# Spectre-SCH_SH2__rev.net
KiCad netlist of a schematic drawn in Altium Designer
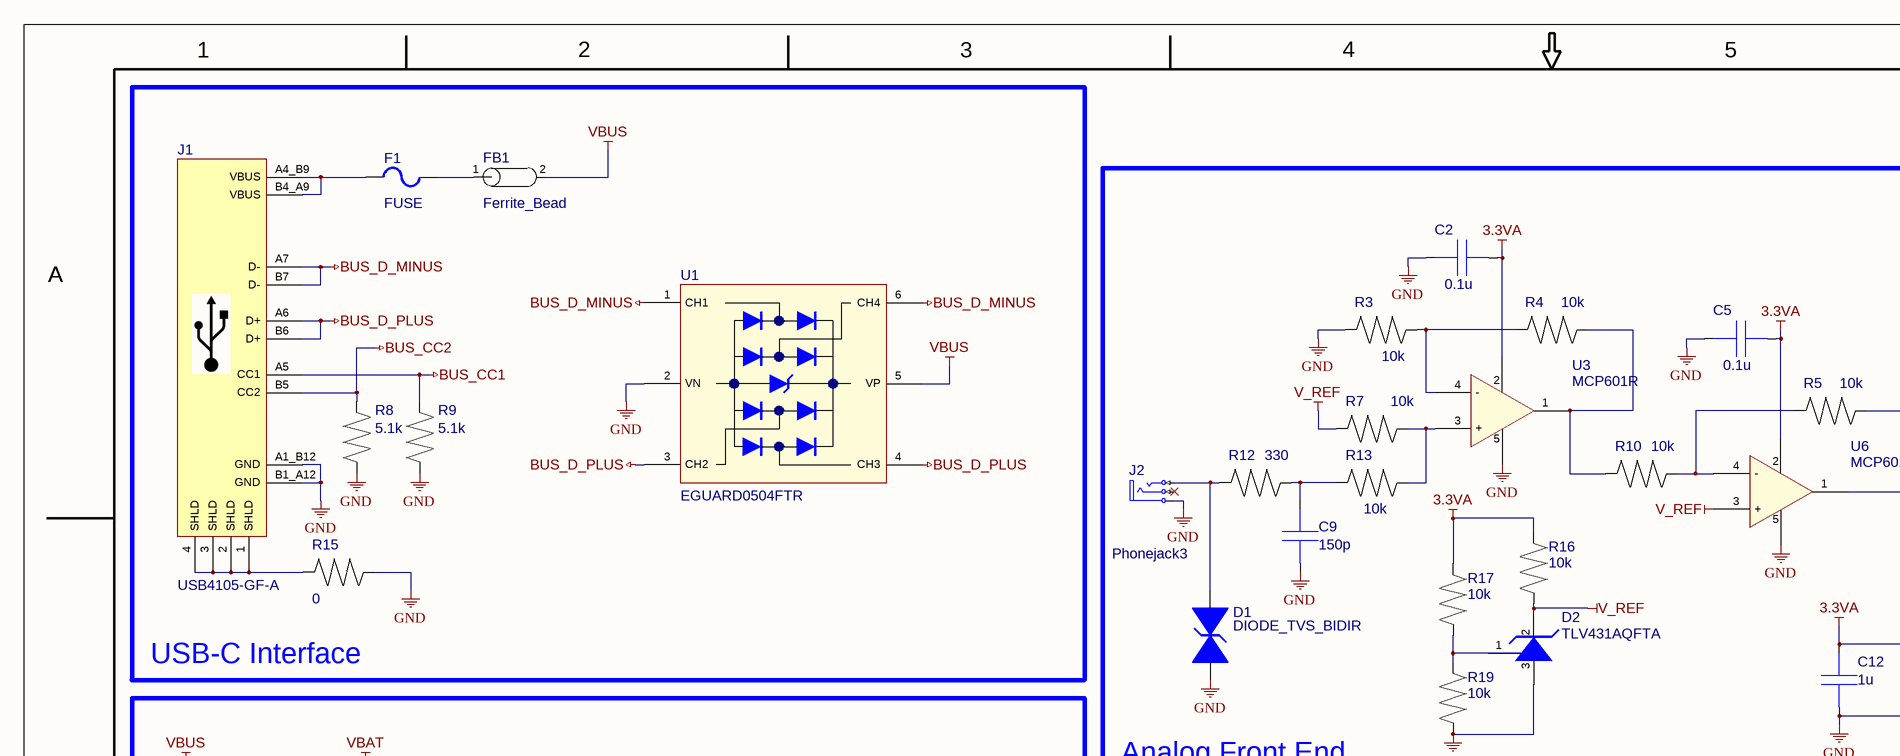
[diagram p0: Spectre-SCH_SH2_(rev).SchDoc, top left]
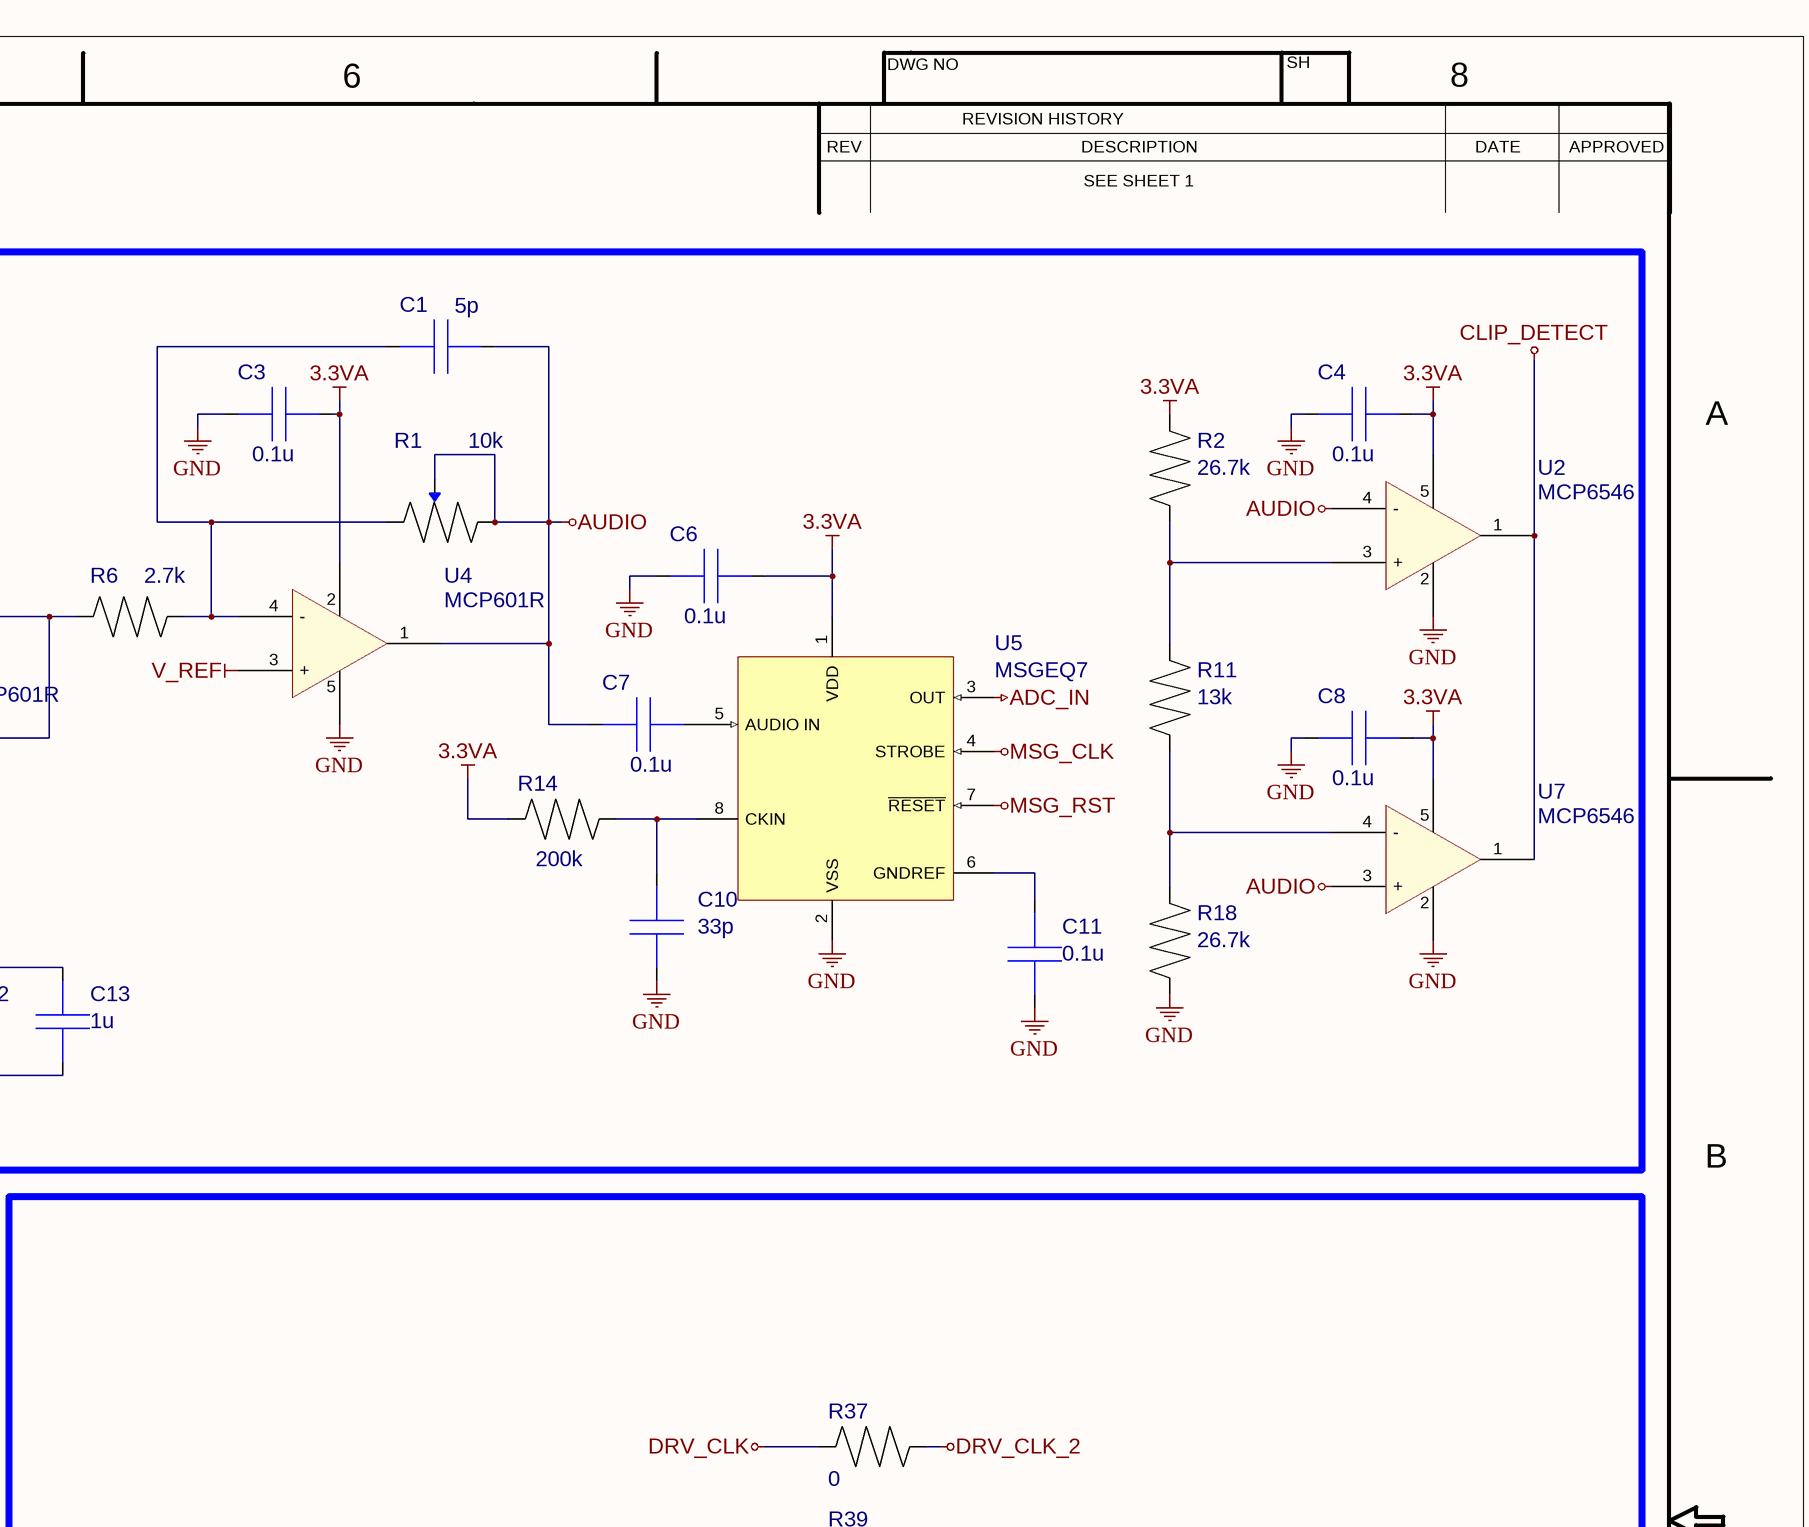
[diagram p1: Spectre-SCH_SH2_(rev).SchDoc, top right]
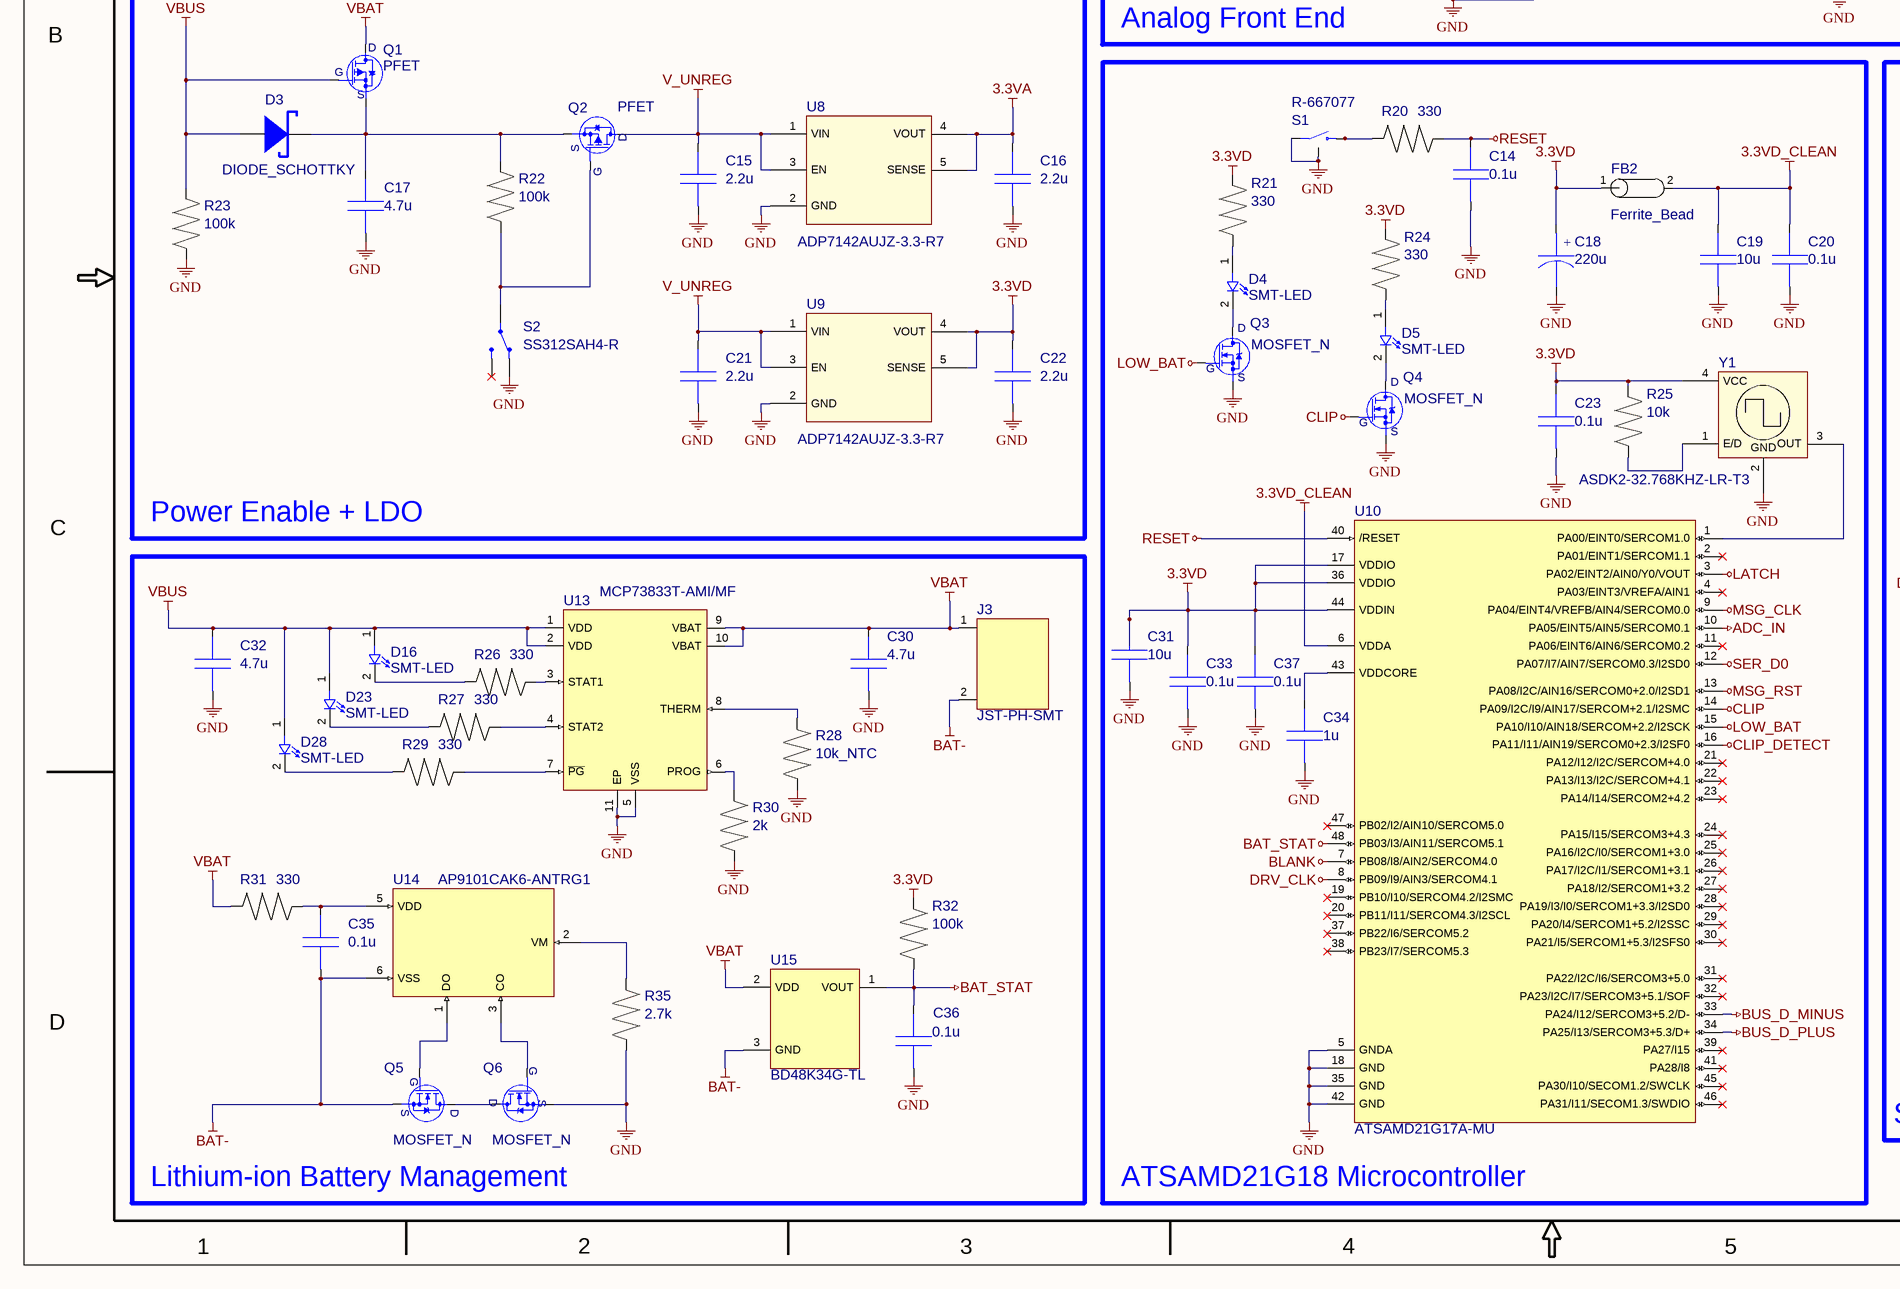
[diagram p2: Spectre-SCH_SH2_(rev).SchDoc, bottom left]
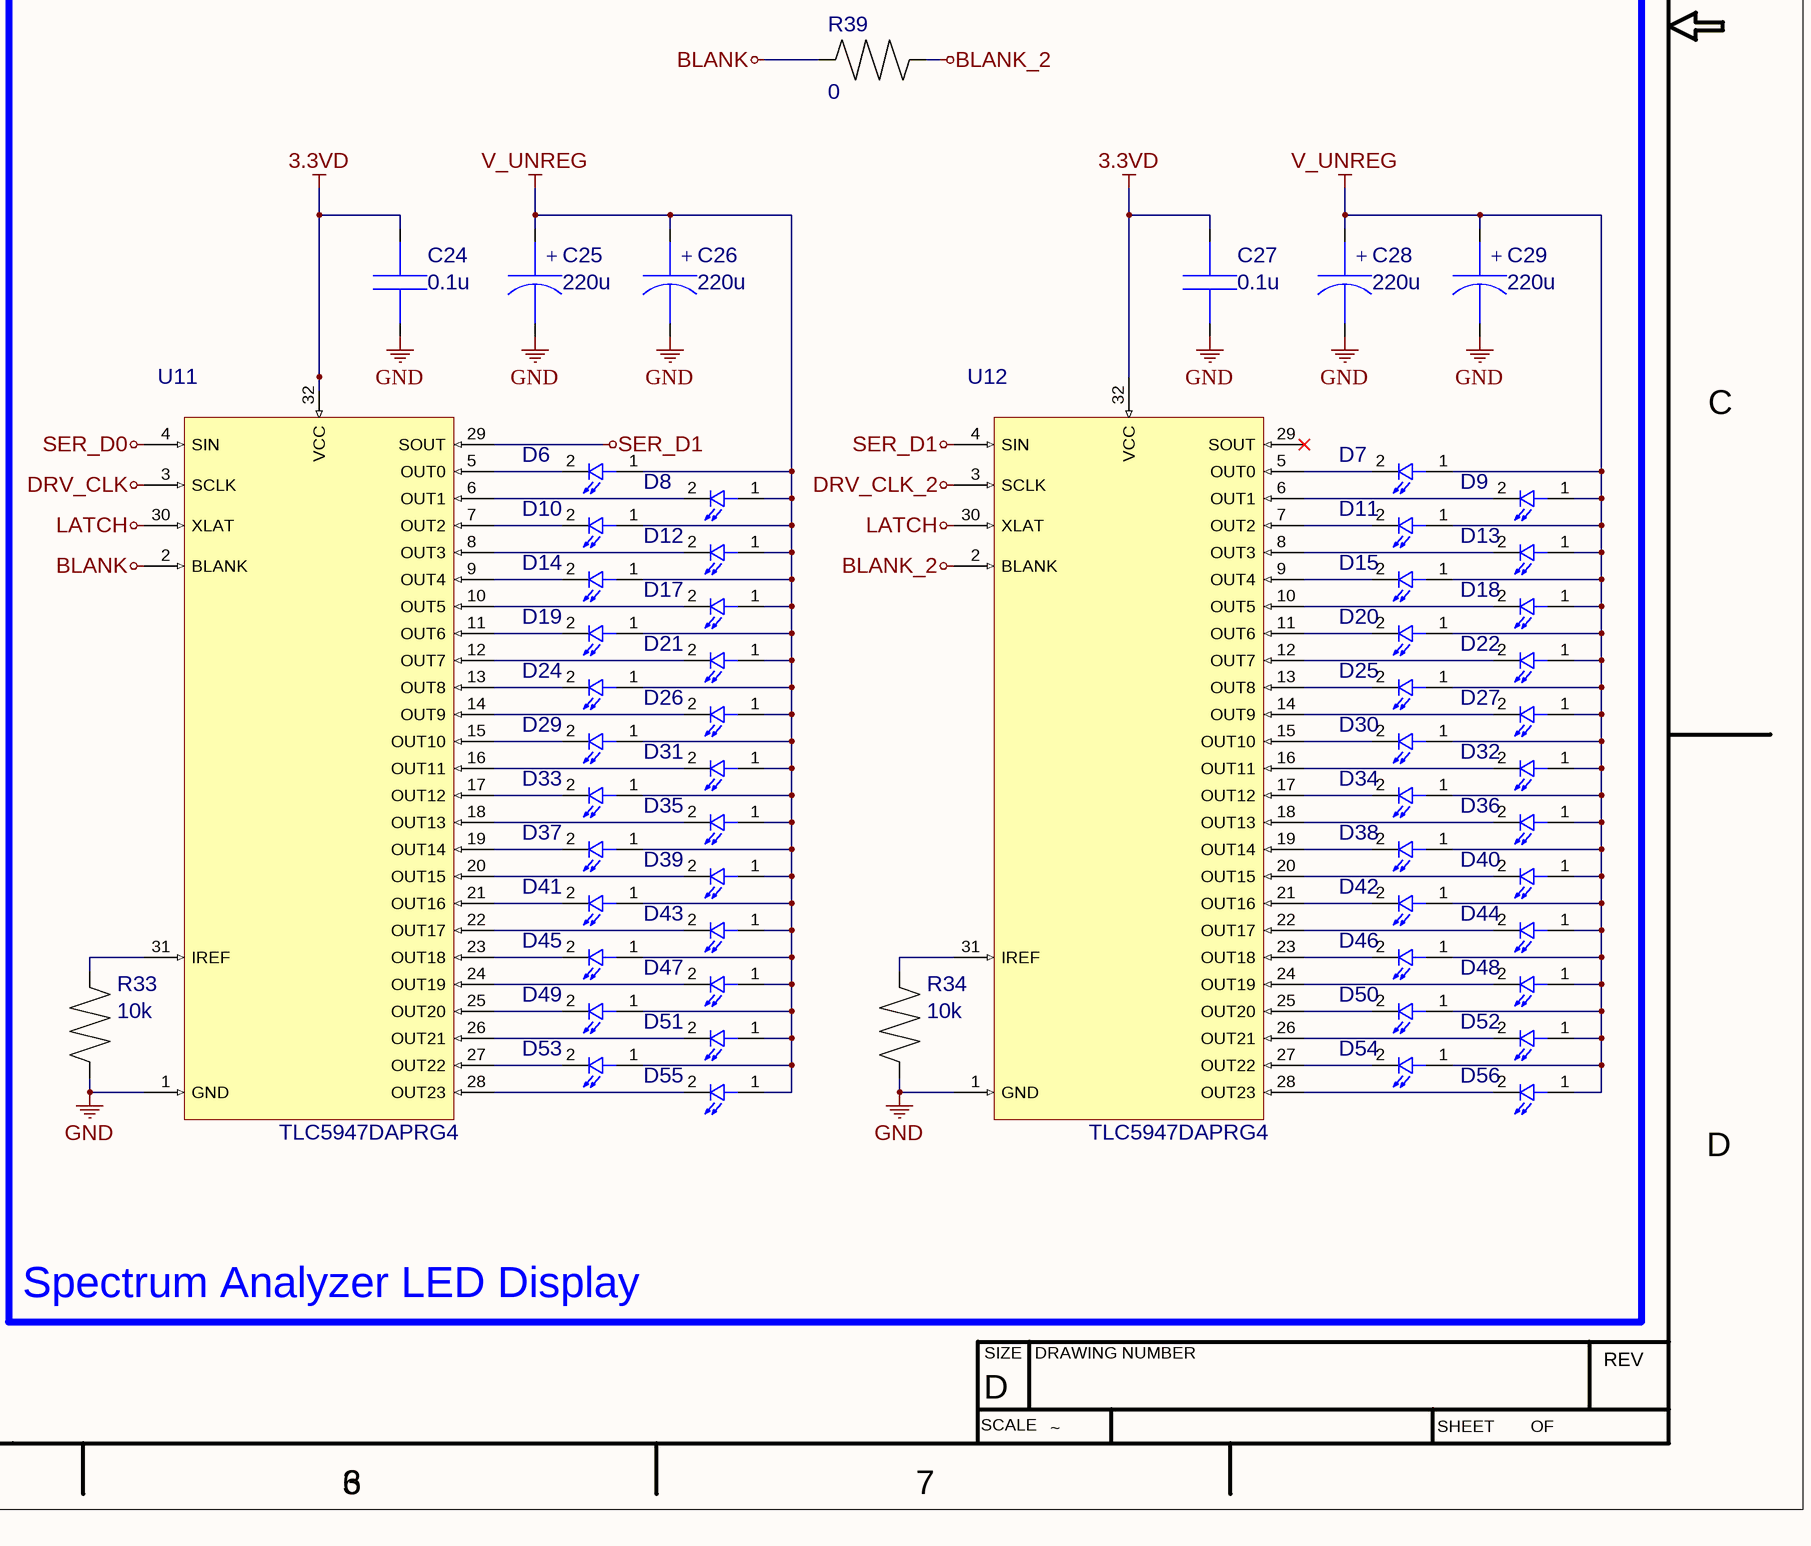
[diagram p3: Spectre-SCH_SH2_(rev).SchDoc, bottom right]

(export (version "E")
  (design (tool "Eeschema 10.0.6"))
  (components
    (comp (ref "C1") (value "5p") (footprint "0805") (libsource (lib "CAPACITORS") (part "CAP")))
    (comp (ref "C2") (value "0.1u") (footprint "0805") (libsource (lib "CAPACITORS") (part "CAP")))
    (comp (ref "C3") (value "0.1u") (footprint "0805") (libsource (lib "CAPACITORS") (part "CAP")))
    (comp (ref "C4") (value "0.1u") (footprint "0805") (libsource (lib "CAPACITORS") (part "CAP")))
    (comp (ref "C5") (value "0.1u") (footprint "0805") (libsource (lib "CAPACITORS") (part "CAP")))
    (comp (ref "C6") (value "0.1u") (footprint "0805") (libsource (lib "CAPACITORS") (part "CAP")))
    (comp (ref "C7") (value "0.1u") (footprint "0805") (libsource (lib "CAPACITORS") (part "CAP")))
    (comp (ref "C8") (value "0.1u") (footprint "0805") (libsource (lib "CAPACITORS") (part "CAP")))
    (comp (ref "C9") (value "150p") (footprint "0805") (libsource (lib "CAPACITORS") (part "CAP")))
    (comp (ref "C10") (value "33p") (footprint "0805") (libsource (lib "CAPACITORS") (part "CAP")))
    (comp (ref "C11") (value "0.1u") (footprint "0805") (libsource (lib "CAPACITORS") (part "CAP")))
    (comp (ref "C12") (value "1u") (footprint "0805") (libsource (lib "CAPACITORS") (part "CAP")))
    (comp (ref "C13") (value "1u") (footprint "0805") (libsource (lib "CAPACITORS") (part "CAP")))
    (comp (ref "C14") (value "0.1u") (footprint "0805") (libsource (lib "CAPACITORS") (part "CAP")))
    (comp (ref "C15") (value "2.2u") (footprint "0805") (libsource (lib "CAPACITORS") (part "CAP")))
    (comp (ref "C16") (value "2.2u") (footprint "0805") (libsource (lib "CAPACITORS") (part "CAP")))
    (comp (ref "C17") (value "4.7u") (footprint "0603") (libsource (lib "CAPACITORS") (part "CAP")))
    (comp (ref "C18")
      (value "220u")
      (footprint "D")
      (description "CAP TANT POLY 220UF 6.3V 2917")
      (fields (field (name "MANUFACTURER") "KEMET") (field (name "PART NUMBER") "T525D227M006ATE025"))
      (libsource (lib "CAPACITORS") (part "CAP_POL"))
    )
    (comp (ref "C19") (value "10u") (footprint "0805") (libsource (lib "CAPACITORS") (part "CAP")))
    (comp (ref "C20") (value "0.1u") (footprint "0805") (libsource (lib "CAPACITORS") (part "CAP")))
    (comp (ref "C21") (value "2.2u") (footprint "0805") (libsource (lib "CAPACITORS") (part "CAP")))
    (comp (ref "C22") (value "2.2u") (footprint "0805") (libsource (lib "CAPACITORS") (part "CAP")))
    (comp (ref "C23") (value "0.1u") (footprint "0805") (libsource (lib "CAPACITORS") (part "CAP")))
    (comp (ref "C24") (value "0.1u") (footprint "0805") (libsource (lib "CAPACITORS") (part "CAP")))
    (comp (ref "C25")
      (value "220u")
      (footprint "D")
      (description "CAP TANT POLY 220UF 6.3V 2917")
      (fields (field (name "MANUFACTURER") "KEMET") (field (name "PART NUMBER") "T525D227M006ATE025"))
      (libsource (lib "CAPACITORS") (part "CAP_POL"))
    )
    (comp (ref "C26")
      (value "220u")
      (footprint "D")
      (description "CAP TANT POLY 220UF 6.3V 2917")
      (fields (field (name "MANUFACTURER") "KEMET") (field (name "PART NUMBER") "T525D227M006ATE025"))
      (libsource (lib "CAPACITORS") (part "CAP_POL"))
    )
    (comp (ref "C27") (value "0.1u") (footprint "0805") (libsource (lib "CAPACITORS") (part "CAP")))
    (comp (ref "C28")
      (value "220u")
      (footprint "D")
      (description "CAP TANT POLY 220UF 6.3V 2917")
      (fields (field (name "MANUFACTURER") "KEMET") (field (name "PART NUMBER") "T525D227M006ATE025"))
      (libsource (lib "CAPACITORS") (part "CAP_POL"))
    )
    (comp (ref "C29")
      (value "220u")
      (footprint "D")
      (description "CAP TANT POLY 220UF 6.3V 2917")
      (fields (field (name "MANUFACTURER") "KEMET") (field (name "PART NUMBER") "T525D227M006ATE025"))
      (libsource (lib "CAPACITORS") (part "CAP_POL"))
    )
    (comp (ref "C30") (value "4.7u") (footprint "0603") (libsource (lib "CAPACITORS") (part "CAP")))
    (comp (ref "C31") (value "10u") (footprint "1206") (libsource (lib "CAPACITORS") (part "CAP")))
    (comp (ref "C32") (value "4.7u") (footprint "0603") (libsource (lib "CAPACITORS") (part "CAP")))
    (comp (ref "C33") (value "0.1u") (footprint "0805") (libsource (lib "CAPACITORS") (part "CAP")))
    (comp (ref "C34") (value "1u") (footprint "0805") (libsource (lib "CAPACITORS") (part "CAP")))
    (comp (ref "C35") (value "0.1u") (footprint "0805") (libsource (lib "CAPACITORS") (part "CAP")))
    (comp (ref "C36") (value "0.1u") (footprint "0805") (libsource (lib "CAPACITORS") (part "CAP")))
    (comp (ref "C37") (value "0.1u") (footprint "0805") (libsource (lib "CAPACITORS") (part "CAP")))
    (comp (ref "D1")
      (value "DIODE_TVS_BIDIR")
      (footprint "0603")
      (description "TVS DIODE BIDIR")
      (libsource (lib "SEMICONDUCTORS") (part "DIODE_TVS_BIDIR"))
    )
    (comp (ref "D2")
      (value "TLV431AQFTA")
      (footprint "SOT-23-3")
      (description "Shunt Voltage Reference IC Adjustable 1.24V 18 VV ±1% 15 mA SOT-23-3")
      (fields (field (name "MANUFACTURER") "Diodes Incorporated"))
      (libsource (lib "TLV431AQFTA") (part "TLV431AQFTA"))
    )
    (comp (ref "D3")
      (value "DIODE_SCHOTTKY")
      (footprint "SMA")
      (description "DIODE SCHOTTKY")
      (libsource (lib "SEMICONDUCTORS") (part "DIODE_SCHOTTKY"))
    )
    (comp (ref "D4") (value "SMT-LED") (footprint "0805 LED") (libsource (lib "SMT-LED") (part "SMT-LED")))
    (comp (ref "D5") (value "SMT-LED") (footprint "0805 LED") (libsource (lib "SMT-LED") (part "SMT-LED")))
    (comp (ref "D6") (value "SMT-LED") (footprint "0805 LED") (libsource (lib "SMT-LED") (part "SMT-LED")))
    (comp (ref "D7") (value "SMT-LED") (footprint "0805 LED") (libsource (lib "SMT-LED") (part "SMT-LED")))
    (comp (ref "D8") (value "SMT-LED") (footprint "0805 LED") (libsource (lib "SMT-LED") (part "SMT-LED")))
    (comp (ref "D9") (value "SMT-LED") (footprint "0805 LED") (libsource (lib "SMT-LED") (part "SMT-LED")))
    (comp (ref "D10") (value "SMT-LED") (footprint "0805 LED") (libsource (lib "SMT-LED") (part "SMT-LED")))
    (comp (ref "D11") (value "SMT-LED") (footprint "0805 LED") (libsource (lib "SMT-LED") (part "SMT-LED")))
    (comp (ref "D12") (value "SMT-LED") (footprint "0805 LED") (libsource (lib "SMT-LED") (part "SMT-LED")))
    (comp (ref "D13") (value "SMT-LED") (footprint "0805 LED") (libsource (lib "SMT-LED") (part "SMT-LED")))
    (comp (ref "D14") (value "SMT-LED") (footprint "0805 LED") (libsource (lib "SMT-LED") (part "SMT-LED")))
    (comp (ref "D15") (value "SMT-LED") (footprint "0805 LED") (libsource (lib "SMT-LED") (part "SMT-LED")))
    (comp (ref "D16") (value "SMT-LED") (footprint "0805 LED") (libsource (lib "SMT-LED") (part "SMT-LED")))
    (comp (ref "D17") (value "SMT-LED") (footprint "0805 LED") (libsource (lib "SMT-LED") (part "SMT-LED")))
    (comp (ref "D18") (value "SMT-LED") (footprint "0805 LED") (libsource (lib "SMT-LED") (part "SMT-LED")))
    (comp (ref "D19") (value "SMT-LED") (footprint "0805 LED") (libsource (lib "SMT-LED") (part "SMT-LED")))
    (comp (ref "D20") (value "SMT-LED") (footprint "0805 LED") (libsource (lib "SMT-LED") (part "SMT-LED")))
    (comp (ref "D21") (value "SMT-LED") (footprint "0805 LED") (libsource (lib "SMT-LED") (part "SMT-LED")))
    (comp (ref "D22") (value "SMT-LED") (footprint "0805 LED") (libsource (lib "SMT-LED") (part "SMT-LED")))
    (comp (ref "D23") (value "SMT-LED") (footprint "0805 LED") (libsource (lib "SMT-LED") (part "SMT-LED")))
    (comp (ref "D24") (value "SMT-LED") (footprint "0805 LED") (libsource (lib "SMT-LED") (part "SMT-LED")))
    (comp (ref "D25") (value "SMT-LED") (footprint "0805 LED") (libsource (lib "SMT-LED") (part "SMT-LED")))
    (comp (ref "D26") (value "SMT-LED") (footprint "0805 LED") (libsource (lib "SMT-LED") (part "SMT-LED")))
    (comp (ref "D27") (value "SMT-LED") (footprint "0805 LED") (libsource (lib "SMT-LED") (part "SMT-LED")))
    (comp (ref "D28") (value "SMT-LED") (footprint "0805 LED") (libsource (lib "SMT-LED") (part "SMT-LED")))
    (comp (ref "D29") (value "SMT-LED") (footprint "0805 LED") (libsource (lib "SMT-LED") (part "SMT-LED")))
    (comp (ref "D30") (value "SMT-LED") (footprint "0805 LED") (libsource (lib "SMT-LED") (part "SMT-LED")))
    (comp (ref "D31") (value "SMT-LED") (footprint "0805 LED") (libsource (lib "SMT-LED") (part "SMT-LED")))
    (comp (ref "D32") (value "SMT-LED") (footprint "0805 LED") (libsource (lib "SMT-LED") (part "SMT-LED")))
    (comp (ref "D33") (value "SMT-LED") (footprint "0805 LED") (libsource (lib "SMT-LED") (part "SMT-LED")))
    (comp (ref "D34") (value "SMT-LED") (footprint "0805 LED") (libsource (lib "SMT-LED") (part "SMT-LED")))
    (comp (ref "D35") (value "SMT-LED") (footprint "0805 LED") (libsource (lib "SMT-LED") (part "SMT-LED")))
    (comp (ref "D36") (value "SMT-LED") (footprint "0805 LED") (libsource (lib "SMT-LED") (part "SMT-LED")))
    (comp (ref "D37") (value "SMT-LED") (footprint "0805 LED") (libsource (lib "SMT-LED") (part "SMT-LED")))
    (comp (ref "D38") (value "SMT-LED") (footprint "0805 LED") (libsource (lib "SMT-LED") (part "SMT-LED")))
    (comp (ref "D39") (value "SMT-LED") (footprint "0805 LED") (libsource (lib "SMT-LED") (part "SMT-LED")))
    (comp (ref "D40") (value "SMT-LED") (footprint "0805 LED") (libsource (lib "SMT-LED") (part "SMT-LED")))
    (comp (ref "D41") (value "SMT-LED") (footprint "0805 LED") (libsource (lib "SMT-LED") (part "SMT-LED")))
    (comp (ref "D42") (value "SMT-LED") (footprint "0805 LED") (libsource (lib "SMT-LED") (part "SMT-LED")))
    (comp (ref "D43") (value "SMT-LED") (footprint "0805 LED") (libsource (lib "SMT-LED") (part "SMT-LED")))
    (comp (ref "D44") (value "SMT-LED") (footprint "0805 LED") (libsource (lib "SMT-LED") (part "SMT-LED")))
    (comp (ref "D45") (value "SMT-LED") (footprint "0805 LED") (libsource (lib "SMT-LED") (part "SMT-LED")))
    (comp (ref "D46") (value "SMT-LED") (footprint "0805 LED") (libsource (lib "SMT-LED") (part "SMT-LED")))
    (comp (ref "D47") (value "SMT-LED") (footprint "0805 LED") (libsource (lib "SMT-LED") (part "SMT-LED")))
    (comp (ref "D48") (value "SMT-LED") (footprint "0805 LED") (libsource (lib "SMT-LED") (part "SMT-LED")))
    (comp (ref "D49") (value "SMT-LED") (footprint "0805 LED") (libsource (lib "SMT-LED") (part "SMT-LED")))
    (comp (ref "D50") (value "SMT-LED") (footprint "0805 LED") (libsource (lib "SMT-LED") (part "SMT-LED")))
    (comp (ref "D51") (value "SMT-LED") (footprint "0805 LED") (libsource (lib "SMT-LED") (part "SMT-LED")))
    (comp (ref "D52") (value "SMT-LED") (footprint "0805 LED") (libsource (lib "SMT-LED") (part "SMT-LED")))
    (comp (ref "D53") (value "SMT-LED") (footprint "0805 LED") (libsource (lib "SMT-LED") (part "SMT-LED")))
    (comp (ref "D54") (value "SMT-LED") (footprint "0805 LED") (libsource (lib "SMT-LED") (part "SMT-LED")))
    (comp (ref "D55") (value "SMT-LED") (footprint "0805 LED") (libsource (lib "SMT-LED") (part "SMT-LED")))
    (comp (ref "D56") (value "SMT-LED") (footprint "0805 LED") (libsource (lib "SMT-LED") (part "SMT-LED")))
    (comp (ref "F1") (value "FUSE") (footprint "1206") (libsource (lib "Power") (part "FUSE")))
    (comp (ref "FB1")
      (value "Ferrite_Bead")
      (footprint "0805")
      (description "Ferrite Bead")
      (libsource (lib "Ferrite_Beads") (part "Ferrite_Bead"))
    )
    (comp (ref "FB2")
      (value "Ferrite_Bead")
      (footprint "0805")
      (description "Ferrite Bead")
      (libsource (lib "Ferrite_Beads") (part "Ferrite_Bead"))
    )
    (comp (ref "J1")
      (value "USB4105-GF-A")
      (footprint "USB4105-GF-A")
      (fields (field (name "MANUFACTURER") "GCT"))
      (libsource (lib "USB4105-GF-A") (part "USB4105-GF-A"))
    )
    (comp (ref "J2")
      (value "Phonejack3")
      (footprint "STX-3500-3NTR")
      (description "Jack Socket, 1/4\" [6.5mm], Thru-Hole, Vertical, 3-Conductor Open Circuit (Non-Normalling)")
      (fields (field (name "PUBLISHER") "Altium Limited"))
      (libsource (lib "Miscellaneous Connectors") (part "Phonejack3"))
    )
    (comp (ref "J3")
      (value "JST-PH-SMT")
      (footprint "JST-PH-SMT")
      (libsource (lib "JST-PH-SMT") (part "JST-PH-SMT"))
    )
    (comp (ref "Q1")
      (value "PFET")
      (footprint "TO-252-3")
      (description "MOSFET, P CH, 3-PIN")
      (libsource (lib "SEMICONDUCTORS") (part "MOSFET_P"))
    )
    (comp (ref "Q2")
      (value "PFET")
      (footprint "TO-252-3")
      (description "MOSFET, P CH, 3-PIN")
      (libsource (lib "") (part "MOSFET_P_1"))
    )
    (comp (ref "Q3")
      (value "MOSFET_N")
      (footprint "SOT-23")
      (description "MOSFET, N CH, 3-PIN")
      (libsource (lib "") (part "MOSFET_N_2"))
    )
    (comp (ref "Q4")
      (value "MOSFET_N")
      (footprint "SOT-23")
      (description "MOSFET, N CH, 3-PIN")
      (libsource (lib "") (part "MOSFET_N_2"))
    )
    (comp (ref "Q5")
      (value "MOSFET_N")
      (footprint "SOT-23")
      (description "MOSFET, N CH, 3-PIN")
      (libsource (lib "SEMICONDUCTORS") (part "MOSFET_N"))
    )
    (comp (ref "Q6")
      (value "MOSFET_N")
      (footprint "SOT-23")
      (description "MOSFET, N CH, 3-PIN")
      (libsource (lib "") (part "MOSFET_N_1"))
    )
    (comp (ref "R1")
      (value "10k")
      (footprint "Adafruit 356")
      (description "10 kOhms - PC Pin Through Hole Trimmer Potentiometer - Turn Top Adjustment")
      (fields (field (name "MANUFACTURER") "Adafruit Industries LLC") (field (name "PART NUMBER") "356"))
      (libsource (lib "ADAFRUIT-10K") (part "Adafruit 356"))
    )
    (comp (ref "R2")
      (value "26.7k")
      (footprint "0805")
      (description "RESISTOR")
      (libsource (lib "RESISTORS") (part "RES"))
    )
    (comp (ref "R3")
      (value "10k")
      (footprint "0805")
      (description "RESISTOR")
      (libsource (lib "RESISTORS") (part "RES"))
    )
    (comp (ref "R4")
      (value "10k")
      (footprint "0805")
      (description "RESISTOR")
      (libsource (lib "RESISTORS") (part "RES"))
    )
    (comp (ref "R5")
      (value "10k")
      (footprint "0805")
      (description "RESISTOR")
      (libsource (lib "RESISTORS") (part "RES"))
    )
    (comp (ref "R6")
      (value "2.7k")
      (footprint "0805")
      (description "RESISTOR")
      (libsource (lib "RESISTORS") (part "RES"))
    )
    (comp (ref "R7")
      (value "10k")
      (footprint "0805")
      (description "RESISTOR")
      (libsource (lib "RESISTORS") (part "RES"))
    )
    (comp (ref "R8")
      (value "5.1k")
      (footprint "0805")
      (description "RESISTOR")
      (libsource (lib "RESISTORS") (part "RES"))
    )
    (comp (ref "R9")
      (value "5.1k")
      (footprint "0805")
      (description "RESISTOR")
      (libsource (lib "RESISTORS") (part "RES"))
    )
    (comp (ref "R10")
      (value "10k")
      (footprint "0805")
      (description "RESISTOR")
      (libsource (lib "RESISTORS") (part "RES"))
    )
    (comp (ref "R11")
      (value "13k")
      (footprint "0805")
      (description "RESISTOR")
      (libsource (lib "RESISTORS") (part "RES"))
    )
    (comp (ref "R12")
      (value "330")
      (footprint "0805")
      (description "RESISTOR")
      (libsource (lib "RESISTORS") (part "RES"))
    )
    (comp (ref "R13")
      (value "10k")
      (footprint "0805")
      (description "RESISTOR")
      (libsource (lib "RESISTORS") (part "RES"))
    )
    (comp (ref "R14")
      (value "200k")
      (footprint "0805")
      (description "RESISTOR")
      (libsource (lib "RESISTORS") (part "RES"))
    )
    (comp (ref "R15")
      (value "0")
      (footprint "0805")
      (description "RESISTOR")
      (libsource (lib "RESISTORS") (part "RES"))
    )
    (comp (ref "R16")
      (value "10k")
      (footprint "0805")
      (description "RESISTOR")
      (libsource (lib "RESISTORS") (part "RES"))
    )
    (comp (ref "R17")
      (value "10k")
      (footprint "0805")
      (description "RESISTOR")
      (libsource (lib "RESISTORS") (part "RES"))
    )
    (comp (ref "R18")
      (value "26.7k")
      (footprint "0805")
      (description "RESISTOR")
      (libsource (lib "RESISTORS") (part "RES"))
    )
    (comp (ref "R19")
      (value "10k")
      (footprint "0805")
      (description "RESISTOR")
      (libsource (lib "RESISTORS") (part "RES"))
    )
    (comp (ref "R20")
      (value "330")
      (footprint "0805")
      (description "RESISTOR")
      (libsource (lib "RESISTORS") (part "RES"))
    )
    (comp (ref "R21")
      (value "330")
      (footprint "0805")
      (description "RESISTOR")
      (libsource (lib "RESISTORS") (part "RES"))
    )
    (comp (ref "R22")
      (value "100k")
      (footprint "0805")
      (description "RESISTOR")
      (libsource (lib "RESISTORS") (part "RES"))
    )
    (comp (ref "R23")
      (value "100k")
      (footprint "0805")
      (description "RESISTOR")
      (libsource (lib "RESISTORS") (part "RES"))
    )
    (comp (ref "R24")
      (value "330")
      (footprint "0805")
      (description "RESISTOR")
      (libsource (lib "RESISTORS") (part "RES"))
    )
    (comp (ref "R25")
      (value "10k")
      (footprint "0805")
      (description "RESISTOR")
      (libsource (lib "RESISTORS") (part "RES"))
    )
    (comp (ref "R26")
      (value "330")
      (footprint "0805")
      (description "RESISTOR")
      (libsource (lib "RESISTORS") (part "RES"))
    )
    (comp (ref "R27")
      (value "330")
      (footprint "0805")
      (description "RESISTOR")
      (libsource (lib "RESISTORS") (part "RES"))
    )
    (comp (ref "R28")
      (value "10k_NTC")
      (footprint "0805")
      (description "RESISTOR")
      (libsource (lib "RESISTORS") (part "RES"))
    )
    (comp (ref "R29")
      (value "330")
      (footprint "0805")
      (description "RESISTOR")
      (libsource (lib "RESISTORS") (part "RES"))
    )
    (comp (ref "R30")
      (value "2k")
      (footprint "0805")
      (description "RESISTOR")
      (libsource (lib "RESISTORS") (part "RES"))
    )
    (comp (ref "R31")
      (value "330")
      (footprint "0805")
      (description "RESISTOR")
      (libsource (lib "RESISTORS") (part "RES"))
    )
    (comp (ref "R32")
      (value "100k")
      (footprint "0805")
      (description "RESISTOR")
      (libsource (lib "RESISTORS") (part "RES"))
    )
    (comp (ref "R33")
      (value "10k")
      (footprint "0805")
      (description "RESISTOR")
      (libsource (lib "RESISTORS") (part "RES"))
    )
    (comp (ref "R34")
      (value "10k")
      (footprint "0805")
      (description "RESISTOR")
      (libsource (lib "RESISTORS") (part "RES"))
    )
    (comp (ref "R35")
      (value "2.7k")
      (footprint "0805")
      (description "RESISTOR")
      (libsource (lib "RESISTORS") (part "RES"))
    )
    (comp (ref "R37")
      (value "0")
      (footprint "0805")
      (description "RESISTOR")
      (libsource (lib "RESISTORS") (part "RES"))
    )
    (comp (ref "R39")
      (value "0")
      (footprint "0805")
      (description "RESISTOR")
      (libsource (lib "RESISTORS") (part "RES"))
    )
    (comp (ref "S1")
      (value "R-667077")
      (footprint "R-667077")
      (description "Tactile Switch SPST-NO Top Actuated Surface Mount")
      (fields (field (name "MANUFACTURER") "Mitsumi Electric Company Ltd"))
      (libsource (lib "R-667077") (part "R-667077"))
    )
    (comp (ref "S2")
      (value "SS312SAH4-R")
      (footprint "SW_SS312SAH4-R")
      (description "Slide Switch SPDT Surface Mount, Right Angle")
      (fields (field (name "MANUFACTURER") "NKK Switches"))
      (libsource (lib "SS312SAH4-R") (part "SS312SAH4-R"))
    )
    (comp (ref "U1")
      (value "EGUARD0504FTR")
      (footprint "TSOP65P120X90-6N")
      (libsource (lib "EGUARD0504FTR") (part "EGUARD0504FTR"))
    )
    (comp (ref "U2")
      (value "MCP6546")
      (footprint "PCBComponent_1")
      (libsource (lib "MCP6546") (part "MCP6546"))
    )
    (comp (ref "U3")
      (value "MCP601R")
      (footprint "PCBComponent_1")
      (libsource (lib "MCP601R") (part "MCP601R"))
    )
    (comp (ref "U4")
      (value "MCP601R")
      (footprint "PCBComponent_1")
      (libsource (lib "MCP601R") (part "MCP601R"))
    )
    (comp (ref "U5") (value "MSGEQ7") (footprint "MSGEQ7") (libsource (lib "MSGEQ7") (part "MSGEQ7")))
    (comp (ref "U6")
      (value "MCP601R")
      (footprint "PCBComponent_1")
      (libsource (lib "MCP601R") (part "MCP601R"))
    )
    (comp (ref "U7")
      (value "MCP6546")
      (footprint "PCBComponent_1")
      (libsource (lib "MCP6546") (part "MCP6546"))
    )
    (comp (ref "U8")
      (value "ADP7142AUJZ-3.3-R7")
      (footprint "TSOT-23-5")
      (libsource (lib "ADP7142AUJZ-3.3-R7") (part "ADP7142AUJZ-3.3-R7"))
    )
    (comp (ref "U9")
      (value "ADP7142AUJZ-3.3-R7")
      (footprint "TSOT-23-5")
      (libsource (lib "ADP7142AUJZ-3.3-R7") (part "ADP7142AUJZ-3.3-R7"))
    )
    (comp (ref "U10")
      (value "ATSAMD21G17A-MU")
      (footprint "ATSAMD21G17A-MU")
      (libsource (lib "ATSAMD21G17A-MU") (part "ATSAMD21G17A-MU"))
    )
    (comp (ref "U11")
      (value "TLC5947DAPRG4")
      (footprint "*SOP65P810X120-32N")
      (libsource (lib "TLC5947DAPRG4") (part "TLC5947DAPRG4"))
    )
    (comp (ref "U12")
      (value "TLC5947DAPRG4")
      (footprint "*SOP65P810X120-32N")
      (libsource (lib "TLC5947DAPRG4") (part "TLC5947DAPRG4"))
    )
    (comp (ref "U13")
      (value "MCP73833T-AMI/MF")
      (footprint "PCBComponent_1")
      (description "Charger IC Lithium Ion/Polymer 10-DFN _3x3_")
      (fields (field (name "MF") "Microchip"))
      (libsource (lib "MCP73833T-AMI_MF") (part "MCP73833T-AMI/MF"))
    )
    (comp (ref "U14")
      (value "AP9101CAK6-ANTRG1")
      (footprint "AP9101CAK6-ANTRG1:SOT-25")
      (description "Ic Batt Prot Li-Ion 1-Cell Sot26")
      (libsource (lib "AP9101CAK6-ANTRG1") (part "AP9101CAK6-ANTRG1"))
    )
    (comp (ref "U15")
      (value "BD48K34G-TL")
      (footprint "SOT-23-3")
      (description "Supervisor Open Drain or Open Collector 1 Channel 3-SSOP")
      (libsource (lib "BD48K34G-TL") (part "BD48K34G-TL"))
    )
    (comp (ref "Y1")
      (value "ASDK2-32.768KHZ-LR-T3")
      (footprint "ASDK2-32.768KHZ-LR-T3")
      (libsource (lib "ASDK2-32.768KHZ-LR-T3") (part "ASDK2-32.768KHZ-LR-T3"))
    )
  )
  (nets
    (net (code "1") (name "3.3VA") (class "Default")
      (node (ref "C12") (pin "2") (pinfunction "2_2") (pintype "passive"))
      (node (ref "C13") (pin "2") (pinfunction "2_2") (pintype "passive"))
      (node (ref "C16") (pin "2") (pinfunction "2_2") (pintype "passive"))
      (node (ref "C2") (pin "1") (pinfunction "1_1") (pintype "passive"))
      (node (ref "C3") (pin "1") (pinfunction "1_1") (pintype "passive"))
      (node (ref "C4") (pin "1") (pinfunction "1_1") (pintype "passive"))
      (node (ref "C5") (pin "1") (pinfunction "1_1") (pintype "passive"))
      (node (ref "C6") (pin "1") (pinfunction "1_1") (pintype "passive"))
      (node (ref "C8") (pin "1") (pinfunction "1_1") (pintype "passive"))
      (node (ref "R14") (pin "2") (pinfunction "2_2") (pintype "passive"))
      (node (ref "R16") (pin "1") (pinfunction "1_1") (pintype "passive"))
      (node (ref "R17") (pin "1") (pinfunction "1_1") (pintype "passive"))
      (node (ref "R2") (pin "2") (pinfunction "2_2") (pintype "passive"))
      (node (ref "U2") (pin "5") (pinfunction "V+_5") (pintype "passive"))
      (node (ref "U3") (pin "2") (pinfunction "V+_2") (pintype "passive"))
      (node (ref "U4") (pin "2") (pinfunction "V+_2") (pintype "passive"))
      (node (ref "U5") (pin "1") (pinfunction "VDD_1") (pintype "power_in"))
      (node (ref "U6") (pin "2") (pinfunction "V+_2") (pintype "passive"))
      (node (ref "U7") (pin "5") (pinfunction "V+_5") (pintype "passive"))
      (node (ref "U8") (pin "4") (pinfunction "VOUT_4") (pintype "passive"))
      (node (ref "U8") (pin "5") (pinfunction "SENSE_5") (pintype "passive"))
    )
    (net (code "2") (name "3.3VD") (class "Default")
      (node (ref "C18") (pin "1") (pinfunction "1_1") (pintype "passive"))
      (node (ref "C22") (pin "2") (pinfunction "2_2") (pintype "passive"))
      (node (ref "C23") (pin "2") (pinfunction "2_2") (pintype "passive"))
      (node (ref "C24") (pin "2") (pinfunction "2_2") (pintype "passive"))
      (node (ref "C27") (pin "2") (pinfunction "2_2") (pintype "passive"))
      (node (ref "C31") (pin "2") (pinfunction "2_2") (pintype "passive"))
      (node (ref "C33") (pin "2") (pinfunction "2_2") (pintype "passive"))
      (node (ref "C37") (pin "2") (pinfunction "2_2") (pintype "passive"))
      (node (ref "FB2") (pin "1") (pinfunction "1_1") (pintype "passive"))
      (node (ref "R21") (pin "2") (pinfunction "2_2") (pintype "passive"))
      (node (ref "R24") (pin "2") (pinfunction "2_2") (pintype "passive"))
      (node (ref "R25") (pin "2") (pinfunction "2_2") (pintype "passive"))
      (node (ref "R32") (pin "1") (pinfunction "1_1") (pintype "passive"))
      (node (ref "U10") (pin "17") (pinfunction "VDDIO_17") (pintype "power_in"))
      (node (ref "U10") (pin "36") (pinfunction "VDDIO_36") (pintype "power_in"))
      (node (ref "U10") (pin "44") (pinfunction "VDDIN_44") (pintype "power_in"))
      (node (ref "U11") (pin "32") (pinfunction "VCC_32") (pintype "input"))
      (node (ref "U12") (pin "32") (pinfunction "VCC_32") (pintype "input"))
      (node (ref "U9") (pin "4") (pinfunction "VOUT_4") (pintype "passive"))
      (node (ref "U9") (pin "5") (pinfunction "SENSE_5") (pintype "passive"))
      (node (ref "Y1") (pin "4") (pinfunction "VCC_4") (pintype "power_in"))
    )
    (net (code "3") (name "3.3VD_CLEAN") (class "Default")
      (node (ref "C19") (pin "2") (pinfunction "2_2") (pintype "passive"))
      (node (ref "C20") (pin "2") (pinfunction "2_2") (pintype "passive"))
      (node (ref "FB2") (pin "2") (pinfunction "2_2") (pintype "passive"))
      (node (ref "U10") (pin "6") (pinfunction "VDDA_6") (pintype "power_in"))
    )
    (net (code "4") (name "ADC_IN") (class "Default")
      (node (ref "U10") (pin "10") (pinfunction "PA05/EINT5/AIN5/SERCOM0.1_10") (pintype "bidirectional"))
      (node (ref "U5") (pin "3") (pinfunction "OUT_3") (pintype "input"))
    )
    (net (code "5") (name "AUDIO") (class "Default")
      (node (ref "C1") (pin "1") (pinfunction "1_1") (pintype "passive"))
      (node (ref "C7") (pin "2") (pinfunction "2_2") (pintype "passive"))
      (node (ref "R1") (pin "2") (pinfunction "2_2") (pintype "passive"))
      (node (ref "R1") (pin "3") (pinfunction "3_3") (pintype "passive"))
      (node (ref "U2") (pin "4") (pinfunction "-_4") (pintype "passive"))
      (node (ref "U4") (pin "1") (pinfunction "OUT_1") (pintype "passive"))
      (node (ref "U7") (pin "3") (pinfunction "+_3") (pintype "passive"))
    )
    (net (code "6") (name "BAT-") (class "Default")
      (node (ref "C35") (pin "1") (pinfunction "1_1") (pintype "passive"))
      (node (ref "J3") (pin "2") (pinfunction "2_2") (pintype "passive"))
      (node (ref "Q5") (pin "3") (pinfunction "S_3") (pintype "passive"))
      (node (ref "U14") (pin "6") (pinfunction "VSS_6") (pintype "input"))
      (node (ref "U15") (pin "3") (pinfunction "GND_3") (pintype "power_in"))
    )
    (net (code "7") (name "BAT_STAT") (class "Default")
      (node (ref "C36") (pin "2") (pinfunction "2_2") (pintype "passive"))
      (node (ref "R32") (pin "2") (pinfunction "2_2") (pintype "passive"))
      (node (ref "U10") (pin "48") (pinfunction "PB03/I3/AIN11/SERCOM5.1_48") (pintype "bidirectional"))
      (node (ref "U15") (pin "1") (pinfunction "VOUT_1") (pintype "passive"))
    )
    (net (code "8") (name "BLANK") (class "Default")
      (node (ref "R39") (pin "2") (pinfunction "2_2") (pintype "passive"))
      (node (ref "U10") (pin "7") (pinfunction "PB08/I8/AIN2/SERCOM4.0_7") (pintype "bidirectional"))
      (node (ref "U11") (pin "2") (pinfunction "BLANK_2") (pintype "input"))
    )
    (net (code "9") (name "BLANK_2") (class "Default")
      (node (ref "R39") (pin "1") (pinfunction "1_1") (pintype "passive"))
      (node (ref "U12") (pin "2") (pinfunction "BLANK_2") (pintype "input"))
    )
    (net (code "10") (name "BUS_CC1") (class "Default")
      (node (ref "J1") (pin "A5") (pinfunction "CC1_A5") (pintype "passive"))
      (node (ref "R9") (pin "2") (pinfunction "2_2") (pintype "passive"))
    )
    (net (code "11") (name "BUS_CC2") (class "Default")
      (node (ref "J1") (pin "B5") (pinfunction "CC2_B5") (pintype "passive"))
      (node (ref "R8") (pin "2") (pinfunction "2_2") (pintype "passive"))
    )
    (net (code "12") (name "BUS_D_MINUS") (class "Default")
      (node (ref "J1") (pin "A7") (pinfunction "D-_A7") (pintype "passive"))
      (node (ref "J1") (pin "B7") (pinfunction "D-_B7") (pintype "passive"))
      (node (ref "U1") (pin "1") (pinfunction "CH1_1") (pintype "passive"))
      (node (ref "U1") (pin "6") (pinfunction "CH4_6") (pintype "passive"))
      (node (ref "U10") (pin "33") (pinfunction "PA24/I12/SERCOM3+5.2/D-_33") (pintype "bidirectional"))
    )
    (net (code "13") (name "BUS_D_PLUS") (class "Default")
      (node (ref "J1") (pin "A6") (pinfunction "D+_A6") (pintype "passive"))
      (node (ref "J1") (pin "B6") (pinfunction "D+_B6") (pintype "passive"))
      (node (ref "U1") (pin "3") (pinfunction "CH2_3") (pintype "passive"))
      (node (ref "U1") (pin "4") (pinfunction "CH3_4") (pintype "passive"))
      (node (ref "U10") (pin "34") (pinfunction "PA25/I13/SERCOM3+5.3/D+_34") (pintype "bidirectional"))
    )
    (net (code "14") (name "CLIP") (class "Default")
      (node (ref "Q4") (pin "1") (pinfunction "G_1") (pintype "passive"))
      (node (ref "U10") (pin "14") (pinfunction "PA09/I2C/I9/AIN17/SERCOM+2.1/I2SMC_14") (pintype "bidirectional"))
    )
    (net (code "15") (name "CLIP_DETECT") (class "Default")
      (node (ref "U10") (pin "16") (pinfunction "PA11/I11/AIN19/SERCOM0+2.3/I2SF0_16") (pintype "bidirectional"))
      (node (ref "U2") (pin "1") (pinfunction "OUT_1") (pintype "passive"))
      (node (ref "U7") (pin "1") (pinfunction "OUT_1") (pintype "passive"))
    )
    (net (code "16") (name "DRV_CLK") (class "Default")
      (node (ref "R37") (pin "2") (pinfunction "2_2") (pintype "passive"))
      (node (ref "U10") (pin "8") (pinfunction "PB09/I9/AIN3/SERCOM4.1_8") (pintype "bidirectional"))
      (node (ref "U11") (pin "3") (pinfunction "SCLK_3") (pintype "input"))
    )
    (net (code "17") (name "DRV_CLK_2") (class "Default")
      (node (ref "R37") (pin "1") (pinfunction "1_1") (pintype "passive"))
      (node (ref "U12") (pin "3") (pinfunction "SCLK_3") (pintype "input"))
    )
    (net (code "18") (name "GND") (class "Default")
      (node (ref "C10") (pin "2") (pinfunction "2_2") (pintype "passive"))
      (node (ref "C11") (pin "2") (pinfunction "2_2") (pintype "passive"))
      (node (ref "C12") (pin "1") (pinfunction "1_1") (pintype "passive"))
      (node (ref "C13") (pin "1") (pinfunction "1_1") (pintype "passive"))
      (node (ref "C14") (pin "1") (pinfunction "1_1") (pintype "passive"))
      (node (ref "C15") (pin "1") (pinfunction "1_1") (pintype "passive"))
      (node (ref "C16") (pin "1") (pinfunction "1_1") (pintype "passive"))
      (node (ref "C17") (pin "1") (pinfunction "1_1") (pintype "passive"))
      (node (ref "C18") (pin "2") (pinfunction "2_2") (pintype "passive"))
      (node (ref "C19") (pin "1") (pinfunction "1_1") (pintype "passive"))
      (node (ref "C2") (pin "2") (pinfunction "2_2") (pintype "passive"))
      (node (ref "C20") (pin "1") (pinfunction "1_1") (pintype "passive"))
      (node (ref "C21") (pin "1") (pinfunction "1_1") (pintype "passive"))
      (node (ref "C22") (pin "1") (pinfunction "1_1") (pintype "passive"))
      (node (ref "C23") (pin "1") (pinfunction "1_1") (pintype "passive"))
      (node (ref "C24") (pin "1") (pinfunction "1_1") (pintype "passive"))
      (node (ref "C25") (pin "2") (pinfunction "2_2") (pintype "passive"))
      (node (ref "C26") (pin "2") (pinfunction "2_2") (pintype "passive"))
      (node (ref "C27") (pin "1") (pinfunction "1_1") (pintype "passive"))
      (node (ref "C28") (pin "2") (pinfunction "2_2") (pintype "passive"))
      (node (ref "C29") (pin "2") (pinfunction "2_2") (pintype "passive"))
      (node (ref "C3") (pin "2") (pinfunction "2_2") (pintype "passive"))
      (node (ref "C30") (pin "1") (pinfunction "1_1") (pintype "passive"))
      (node (ref "C31") (pin "1") (pinfunction "1_1") (pintype "passive"))
      (node (ref "C32") (pin "1") (pinfunction "1_1") (pintype "passive"))
      (node (ref "C33") (pin "1") (pinfunction "1_1") (pintype "passive"))
      (node (ref "C34") (pin "1") (pinfunction "1_1") (pintype "passive"))
      (node (ref "C36") (pin "1") (pinfunction "1_1") (pintype "passive"))
      (node (ref "C37") (pin "1") (pinfunction "1_1") (pintype "passive"))
      (node (ref "C4") (pin "2") (pinfunction "2_2") (pintype "passive"))
      (node (ref "C5") (pin "2") (pinfunction "2_2") (pintype "passive"))
      (node (ref "C6") (pin "2") (pinfunction "2_2") (pintype "passive"))
      (node (ref "C8") (pin "2") (pinfunction "2_2") (pintype "passive"))
      (node (ref "C9") (pin "1") (pinfunction "1_1") (pintype "passive"))
      (node (ref "D1") (pin "1") (pinfunction "1_1") (pintype "passive"))
      (node (ref "D2") (pin "3") (pinfunction "A_3") (pintype "passive"))
      (node (ref "J1") (pin "A1_B12") (pinfunction "GND_A1_B12") (pintype "passive"))
      (node (ref "J1") (pin "B1_A12") (pinfunction "GND_B1_A12") (pintype "passive"))
      (node (ref "J2") (pin "1") (pinfunction "S_1") (pintype "power_in"))
      (node (ref "Q3") (pin "3") (pinfunction "S_3") (pintype "passive"))
      (node (ref "Q4") (pin "3") (pinfunction "S_3") (pintype "passive"))
      (node (ref "Q6") (pin "3") (pinfunction "S_3") (pintype "passive"))
      (node (ref "R15") (pin "1") (pinfunction "1_1") (pintype "passive"))
      (node (ref "R18") (pin "1") (pinfunction "1_1") (pintype "passive"))
      (node (ref "R19") (pin "2") (pinfunction "2_2") (pintype "passive"))
      (node (ref "R23") (pin "1") (pinfunction "1_1") (pintype "passive"))
      (node (ref "R28") (pin "2") (pinfunction "2_2") (pintype "passive"))
      (node (ref "R3") (pin "2") (pinfunction "2_2") (pintype "passive"))
      (node (ref "R30") (pin "2") (pinfunction "2_2") (pintype "passive"))
      (node (ref "R33") (pin "1") (pinfunction "1_1") (pintype "passive"))
      (node (ref "R34") (pin "1") (pinfunction "1_1") (pintype "passive"))
      (node (ref "R35") (pin "2") (pinfunction "2_2") (pintype "passive"))
      (node (ref "R8") (pin "1") (pinfunction "1_1") (pintype "passive"))
      (node (ref "R9") (pin "1") (pinfunction "1_1") (pintype "passive"))
      (node (ref "S1") (pin "1") (pinfunction "GND_1") (pintype "passive"))
      (node (ref "S1") (pin "2") (pinfunction "NO_2") (pintype "passive"))
      (node (ref "S2") (pin "1") (pinfunction "1_1") (pintype "passive"))
      (node (ref "U1") (pin "2") (pinfunction "VN_2") (pintype "passive"))
      (node (ref "U10") (pin "18") (pinfunction "GND_18") (pintype "power_in"))
      (node (ref "U10") (pin "35") (pinfunction "GND_35") (pintype "power_in"))
      (node (ref "U10") (pin "42") (pinfunction "GND_42") (pintype "power_in"))
      (node (ref "U10") (pin "5") (pinfunction "GNDA_5") (pintype "power_in"))
      (node (ref "U11") (pin "1") (pinfunction "GND_1") (pintype "input"))
      (node (ref "U12") (pin "1") (pinfunction "GND_1") (pintype "input"))
      (node (ref "U13") (pin "11") (pinfunction "EP_11") (pintype "power_in"))
      (node (ref "U13") (pin "5") (pinfunction "VSS_5") (pintype "power_in"))
      (node (ref "U2") (pin "2") (pinfunction "V-_2") (pintype "passive"))
      (node (ref "U3") (pin "5") (pinfunction "V-_5") (pintype "passive"))
      (node (ref "U4") (pin "5") (pinfunction "V-_5") (pintype "passive"))
      (node (ref "U5") (pin "2") (pinfunction "VSS_2") (pintype "power_in"))
      (node (ref "U6") (pin "5") (pinfunction "V-_5") (pintype "passive"))
      (node (ref "U7") (pin "2") (pinfunction "V-_2") (pintype "passive"))
      (node (ref "U8") (pin "2") (pinfunction "GND_2") (pintype "passive"))
      (node (ref "U9") (pin "2") (pinfunction "GND_2") (pintype "passive"))
      (node (ref "Y1") (pin "2") (pinfunction "GND_2") (pintype "passive"))
    )
    (net (code "19") (name "LATCH") (class "Default")
      (node (ref "U10") (pin "3") (pinfunction "PA02/EINT2/AIN0/Y0/VOUT_3") (pintype "bidirectional"))
      (node (ref "U11") (pin "30") (pinfunction "XLAT_30") (pintype "input"))
      (node (ref "U12") (pin "30") (pinfunction "XLAT_30") (pintype "input"))
    )
    (net (code "20") (name "LOW_BAT") (class "Default")
      (node (ref "Q3") (pin "1") (pinfunction "G_1") (pintype "passive"))
      (node (ref "U10") (pin "15") (pinfunction "PA10/I10/AIN18/SERCOM+2.2/I2SCK_15") (pintype "bidirectional"))
    )
    (net (code "21") (name "MSG_CLK") (class "Default")
      (node (ref "U10") (pin "9") (pinfunction "PA04/EINT4/VREFB/AIN4/SERCOM0.0_9") (pintype "bidirectional"))
      (node (ref "U5") (pin "4") (pinfunction "STROBE_4") (pintype "input"))
    )
    (net (code "22") (name "MSG_RST") (class "Default")
      (node (ref "U10") (pin "13") (pinfunction "PA08/I2C/AIN16/SERCOM0+2.0/I2SD1_13") (pintype "bidirectional"))
      (node (ref "U5") (pin "7") (pinfunction "~{RESET}_7") (pintype "input"))
    )
    (net (code "23") (name "Net-(C9-Pad2)") (class "Default")
      (node (ref "C9") (pin "2") (pinfunction "2_2") (pintype "passive"))
      (node (ref "R12") (pin "1") (pinfunction "1_1") (pintype "passive"))
      (node (ref "R13") (pin "2") (pinfunction "2_2") (pintype "passive"))
    )
    (net (code "24") (name "Net-(D2-REF)") (class "Default")
      (node (ref "D2") (pin "1") (pinfunction "REF_1") (pintype "power_in"))
      (node (ref "R17") (pin "2") (pinfunction "2_2") (pintype "passive"))
      (node (ref "R19") (pin "1") (pinfunction "1_1") (pintype "passive"))
    )
    (net (code "25") (name "Net-(D3-K)") (class "Default")
      (node (ref "C17") (pin "2") (pinfunction "2_2") (pintype "passive"))
      (node (ref "D3") (pin "2") (pinfunction "K_2") (pintype "passive"))
      (node (ref "Q1") (pin "3") (pinfunction "S_3") (pintype "passive"))
      (node (ref "Q2") (pin "3") (pinfunction "S_3") (pintype "passive"))
      (node (ref "R22") (pin "2") (pinfunction "2_2") (pintype "passive"))
    )
    (net (code "26") (name "Net-(D4-Pad1)") (class "Default")
      (node (ref "D4") (pin "1") (pinfunction "1_1") (pintype "passive"))
      (node (ref "R21") (pin "1") (pinfunction "1_1") (pintype "passive"))
    )
    (net (code "27") (name "Net-(D5-Pad1)") (class "Default")
      (node (ref "D5") (pin "1") (pinfunction "1_1") (pintype "passive"))
      (node (ref "R24") (pin "1") (pinfunction "1_1") (pintype "passive"))
    )
    (net (code "28") (name "Net-(D16-Pad2)") (class "Default")
      (node (ref "D16") (pin "2") (pinfunction "2_2") (pintype "passive"))
      (node (ref "R26") (pin "2") (pinfunction "2_2") (pintype "passive"))
    )
    (net (code "29") (name "Net-(D23-Pad2)") (class "Default")
      (node (ref "D23") (pin "2") (pinfunction "2_2") (pintype "passive"))
      (node (ref "R27") (pin "2") (pinfunction "2_2") (pintype "passive"))
    )
    (net (code "30") (name "Net-(D28-Pad2)") (class "Default")
      (node (ref "D28") (pin "2") (pinfunction "2_2") (pintype "passive"))
      (node (ref "R29") (pin "2") (pinfunction "2_2") (pintype "passive"))
    )
    (net (code "31") (name "Net-(F1-Pad1)") (class "Default")
      (node (ref "F1") (pin "1") (pinfunction "1_1") (pintype "passive"))
      (node (ref "J1") (pin "A4_B9") (pinfunction "VBUS_A4_B9") (pintype "passive"))
      (node (ref "J1") (pin "B4_A9") (pinfunction "VBUS_B4_A9") (pintype "passive"))
    )
    (net (code "32") (name "Net-(F1-Pad2)") (class "Default")
      (node (ref "F1") (pin "2") (pinfunction "2_2") (pintype "passive"))
      (node (ref "FB1") (pin "1") (pinfunction "1_1") (pintype "passive"))
    )
    (net (code "33") (name "Net-(J1-SHLD-Pad1)") (class "Default")
      (node (ref "J1") (pin "1") (pinfunction "SHLD_1") (pintype "passive"))
      (node (ref "J1") (pin "2") (pinfunction "SHLD_2") (pintype "passive"))
      (node (ref "J1") (pin "3") (pinfunction "SHLD_3") (pintype "passive"))
      (node (ref "J1") (pin "4") (pinfunction "SHLD_4") (pintype "passive"))
      (node (ref "R15") (pin "2") (pinfunction "2_2") (pintype "passive"))
    )
    (net (code "34") (name "Net-(J2-T)") (class "Default")
      (node (ref "D1") (pin "2") (pinfunction "2_2") (pintype "passive"))
      (node (ref "J2") (pin "3") (pinfunction "T_3") (pintype "input"))
      (node (ref "R12") (pin "2") (pinfunction "2_2") (pintype "passive"))
    )
    (net (code "35") (name "Net-(Q2-G)") (class "Default")
      (node (ref "Q2") (pin "1") (pinfunction "G_1") (pintype "passive"))
      (node (ref "R22") (pin "1") (pinfunction "1_1") (pintype "passive"))
      (node (ref "S2") (pin "2") (pinfunction "2_2") (pintype "passive"))
    )
    (net (code "36") (name "Net-(Q3-D)") (class "Default")
      (node (ref "D4") (pin "2") (pinfunction "2_2") (pintype "passive"))
      (node (ref "Q3") (pin "2") (pinfunction "D_2") (pintype "passive"))
    )
    (net (code "37") (name "Net-(Q4-D)") (class "Default")
      (node (ref "D5") (pin "2") (pinfunction "2_2") (pintype "passive"))
      (node (ref "Q4") (pin "2") (pinfunction "D_2") (pintype "passive"))
    )
    (net (code "38") (name "Net-(Q5-D)") (class "Default")
      (node (ref "Q5") (pin "2") (pinfunction "D_2") (pintype "passive"))
      (node (ref "Q6") (pin "2") (pinfunction "D_2") (pintype "passive"))
    )
    (net (code "39") (name "Net-(Q5-G)") (class "Default")
      (node (ref "Q5") (pin "1") (pinfunction "G_1") (pintype "passive"))
      (node (ref "U14") (pin "1") (pinfunction "DO_1") (pintype "input"))
    )
    (net (code "40") (name "Net-(Q6-G)") (class "Default")
      (node (ref "Q6") (pin "1") (pinfunction "G_1") (pintype "passive"))
      (node (ref "U14") (pin "3") (pinfunction "CO_3") (pintype "input"))
    )
    (net (code "41") (name "Net-(R20-Pad2)") (class "Default")
      (node (ref "R20") (pin "2") (pinfunction "2_2") (pintype "passive"))
      (node (ref "S1") (pin "3") (pinfunction "COM_3") (pintype "passive"))
      (node (ref "S1") (pin "4") (pinfunction "COM_4") (pintype "passive"))
      (node (ref "S1") (pin "5") (pinfunction "COM_5") (pintype "passive"))
    )
    (net (code "42") (name "Net-(U2-+)") (class "Default")
      (node (ref "R11") (pin "2") (pinfunction "2_2") (pintype "passive"))
      (node (ref "R2") (pin "1") (pinfunction "1_1") (pintype "passive"))
      (node (ref "U2") (pin "3") (pinfunction "+_3") (pintype "passive"))
    )
    (net (code "43") (name "Net-(U3-+)") (class "Default")
      (node (ref "R13") (pin "1") (pinfunction "1_1") (pintype "passive"))
      (node (ref "R7") (pin "1") (pinfunction "1_1") (pintype "passive"))
      (node (ref "U3") (pin "3") (pinfunction "+_3") (pintype "passive"))
    )
    (net (code "44") (name "Net-(U3--)") (class "Default")
      (node (ref "R3") (pin "1") (pinfunction "1_1") (pintype "passive"))
      (node (ref "R4") (pin "2") (pinfunction "2_2") (pintype "passive"))
      (node (ref "U3") (pin "4") (pinfunction "-_4") (pintype "passive"))
    )
    (net (code "45") (name "Net-(U3-OUT)") (class "Default")
      (node (ref "R10") (pin "2") (pinfunction "2_2") (pintype "passive"))
      (node (ref "R4") (pin "1") (pinfunction "1_1") (pintype "passive"))
      (node (ref "U3") (pin "1") (pinfunction "OUT_1") (pintype "passive"))
    )
    (net (code "46") (name "Net-(U4--)") (class "Default")
      (node (ref "C1") (pin "2") (pinfunction "2_2") (pintype "passive"))
      (node (ref "R1") (pin "1") (pinfunction "1_1") (pintype "passive"))
      (node (ref "R6") (pin "1") (pinfunction "1_1") (pintype "passive"))
      (node (ref "U4") (pin "4") (pinfunction "-_4") (pintype "passive"))
    )
    (net (code "47") (name "Net-(U5-AUDIO_IN)") (class "Default")
      (node (ref "C7") (pin "1") (pinfunction "1_1") (pintype "passive"))
      (node (ref "U5") (pin "5") (pinfunction "AUDIO_IN_5") (pintype "input"))
    )
    (net (code "48") (name "Net-(U5-CKIN)") (class "Default")
      (node (ref "C10") (pin "1") (pinfunction "1_1") (pintype "passive"))
      (node (ref "R14") (pin "1") (pinfunction "1_1") (pintype "passive"))
      (node (ref "U5") (pin "8") (pinfunction "CKIN_8") (pintype "passive"))
    )
    (net (code "49") (name "Net-(U5-GNDREF)") (class "Default")
      (node (ref "C11") (pin "1") (pinfunction "1_1") (pintype "passive"))
      (node (ref "U5") (pin "6") (pinfunction "GNDREF_6") (pintype "power_in"))
    )
    (net (code "50") (name "Net-(U6--)") (class "Default")
      (node (ref "R10") (pin "1") (pinfunction "1_1") (pintype "passive"))
      (node (ref "R5") (pin "2") (pinfunction "2_2") (pintype "passive"))
      (node (ref "U6") (pin "4") (pinfunction "-_4") (pintype "passive"))
    )
    (net (code "51") (name "Net-(U6-OUT)") (class "Default")
      (node (ref "R5") (pin "1") (pinfunction "1_1") (pintype "passive"))
      (node (ref "R6") (pin "2") (pinfunction "2_2") (pintype "passive"))
      (node (ref "U6") (pin "1") (pinfunction "OUT_1") (pintype "passive"))
    )
    (net (code "52") (name "Net-(U7--)") (class "Default")
      (node (ref "R11") (pin "1") (pinfunction "1_1") (pintype "passive"))
      (node (ref "R18") (pin "2") (pinfunction "2_2") (pintype "passive"))
      (node (ref "U7") (pin "4") (pinfunction "-_4") (pintype "passive"))
    )
    (net (code "53") (name "Net-(U10-PA00{slash}EINT0{slash}SERCOM1.0)") (class "Default")
      (node (ref "U10") (pin "1") (pinfunction "PA00/EINT0/SERCOM1.0_1") (pintype "bidirectional"))
      (node (ref "Y1") (pin "3") (pinfunction "OUT_3") (pintype "passive"))
    )
    (net (code "54") (name "Net-(U10-VDDCORE)") (class "Default")
      (node (ref "C34") (pin "2") (pinfunction "2_2") (pintype "passive"))
      (node (ref "U10") (pin "43") (pinfunction "VDDCORE_43") (pintype "power_in"))
    )
    (net (code "55") (name "Net-(U11-IREF)") (class "Default")
      (node (ref "R33") (pin "2") (pinfunction "2_2") (pintype "passive"))
      (node (ref "U11") (pin "31") (pinfunction "IREF_31") (pintype "input"))
    )
    (net (code "56") (name "Net-(U11-OUT0)") (class "Default")
      (node (ref "D6") (pin "2") (pinfunction "2_2") (pintype "passive"))
      (node (ref "U11") (pin "5") (pinfunction "OUT0_5") (pintype "input"))
    )
    (net (code "57") (name "Net-(U11-OUT1)") (class "Default")
      (node (ref "D8") (pin "2") (pinfunction "2_2") (pintype "passive"))
      (node (ref "U11") (pin "6") (pinfunction "OUT1_6") (pintype "input"))
    )
    (net (code "58") (name "Net-(U11-OUT2)") (class "Default")
      (node (ref "D10") (pin "2") (pinfunction "2_2") (pintype "passive"))
      (node (ref "U11") (pin "7") (pinfunction "OUT2_7") (pintype "input"))
    )
    (net (code "59") (name "Net-(U11-OUT3)") (class "Default")
      (node (ref "D12") (pin "2") (pinfunction "2_2") (pintype "passive"))
      (node (ref "U11") (pin "8") (pinfunction "OUT3_8") (pintype "input"))
    )
    (net (code "60") (name "Net-(U11-OUT4)") (class "Default")
      (node (ref "D14") (pin "2") (pinfunction "2_2") (pintype "passive"))
      (node (ref "U11") (pin "9") (pinfunction "OUT4_9") (pintype "input"))
    )
    (net (code "61") (name "Net-(U11-OUT5)") (class "Default")
      (node (ref "D17") (pin "2") (pinfunction "2_2") (pintype "passive"))
      (node (ref "U11") (pin "10") (pinfunction "OUT5_10") (pintype "input"))
    )
    (net (code "62") (name "Net-(U11-OUT6)") (class "Default")
      (node (ref "D19") (pin "2") (pinfunction "2_2") (pintype "passive"))
      (node (ref "U11") (pin "11") (pinfunction "OUT6_11") (pintype "input"))
    )
    (net (code "63") (name "Net-(U11-OUT7)") (class "Default")
      (node (ref "D21") (pin "2") (pinfunction "2_2") (pintype "passive"))
      (node (ref "U11") (pin "12") (pinfunction "OUT7_12") (pintype "input"))
    )
    (net (code "64") (name "Net-(U11-OUT8)") (class "Default")
      (node (ref "D24") (pin "2") (pinfunction "2_2") (pintype "passive"))
      (node (ref "U11") (pin "13") (pinfunction "OUT8_13") (pintype "input"))
    )
    (net (code "65") (name "Net-(U11-OUT9)") (class "Default")
      (node (ref "D26") (pin "2") (pinfunction "2_2") (pintype "passive"))
      (node (ref "U11") (pin "14") (pinfunction "OUT9_14") (pintype "input"))
    )
    (net (code "66") (name "Net-(U11-OUT10)") (class "Default")
      (node (ref "D29") (pin "2") (pinfunction "2_2") (pintype "passive"))
      (node (ref "U11") (pin "15") (pinfunction "OUT10_15") (pintype "input"))
    )
    (net (code "67") (name "Net-(U11-OUT11)") (class "Default")
      (node (ref "D31") (pin "2") (pinfunction "2_2") (pintype "passive"))
      (node (ref "U11") (pin "16") (pinfunction "OUT11_16") (pintype "input"))
    )
    (net (code "68") (name "Net-(U11-OUT12)") (class "Default")
      (node (ref "D33") (pin "2") (pinfunction "2_2") (pintype "passive"))
      (node (ref "U11") (pin "17") (pinfunction "OUT12_17") (pintype "input"))
    )
    (net (code "69") (name "Net-(U11-OUT13)") (class "Default")
      (node (ref "D35") (pin "2") (pinfunction "2_2") (pintype "passive"))
      (node (ref "U11") (pin "18") (pinfunction "OUT13_18") (pintype "input"))
    )
    (net (code "70") (name "Net-(U11-OUT14)") (class "Default")
      (node (ref "D37") (pin "2") (pinfunction "2_2") (pintype "passive"))
      (node (ref "U11") (pin "19") (pinfunction "OUT14_19") (pintype "input"))
    )
    (net (code "71") (name "Net-(U11-OUT15)") (class "Default")
      (node (ref "D39") (pin "2") (pinfunction "2_2") (pintype "passive"))
      (node (ref "U11") (pin "20") (pinfunction "OUT15_20") (pintype "input"))
    )
    (net (code "72") (name "Net-(U11-OUT16)") (class "Default")
      (node (ref "D41") (pin "2") (pinfunction "2_2") (pintype "passive"))
      (node (ref "U11") (pin "21") (pinfunction "OUT16_21") (pintype "input"))
    )
    (net (code "73") (name "Net-(U11-OUT17)") (class "Default")
      (node (ref "D43") (pin "2") (pinfunction "2_2") (pintype "passive"))
      (node (ref "U11") (pin "22") (pinfunction "OUT17_22") (pintype "input"))
    )
    (net (code "74") (name "Net-(U11-OUT18)") (class "Default")
      (node (ref "D45") (pin "2") (pinfunction "2_2") (pintype "passive"))
      (node (ref "U11") (pin "23") (pinfunction "OUT18_23") (pintype "input"))
    )
    (net (code "75") (name "Net-(U11-OUT19)") (class "Default")
      (node (ref "D47") (pin "2") (pinfunction "2_2") (pintype "passive"))
      (node (ref "U11") (pin "24") (pinfunction "OUT19_24") (pintype "input"))
    )
    (net (code "76") (name "Net-(U11-OUT20)") (class "Default")
      (node (ref "D49") (pin "2") (pinfunction "2_2") (pintype "passive"))
      (node (ref "U11") (pin "25") (pinfunction "OUT20_25") (pintype "input"))
    )
    (net (code "77") (name "Net-(U11-OUT21)") (class "Default")
      (node (ref "D51") (pin "2") (pinfunction "2_2") (pintype "passive"))
      (node (ref "U11") (pin "26") (pinfunction "OUT21_26") (pintype "input"))
    )
    (net (code "78") (name "Net-(U11-OUT22)") (class "Default")
      (node (ref "D53") (pin "2") (pinfunction "2_2") (pintype "passive"))
      (node (ref "U11") (pin "27") (pinfunction "OUT22_27") (pintype "input"))
    )
    (net (code "79") (name "Net-(U11-OUT23)") (class "Default")
      (node (ref "D55") (pin "2") (pinfunction "2_2") (pintype "passive"))
      (node (ref "U11") (pin "28") (pinfunction "OUT23_28") (pintype "input"))
    )
    (net (code "80") (name "Net-(U12-IREF)") (class "Default")
      (node (ref "R34") (pin "2") (pinfunction "2_2") (pintype "passive"))
      (node (ref "U12") (pin "31") (pinfunction "IREF_31") (pintype "input"))
    )
    (net (code "81") (name "Net-(U12-OUT0)") (class "Default")
      (node (ref "D7") (pin "2") (pinfunction "2_2") (pintype "passive"))
      (node (ref "U12") (pin "5") (pinfunction "OUT0_5") (pintype "input"))
    )
    (net (code "82") (name "Net-(U12-OUT1)") (class "Default")
      (node (ref "D9") (pin "2") (pinfunction "2_2") (pintype "passive"))
      (node (ref "U12") (pin "6") (pinfunction "OUT1_6") (pintype "input"))
    )
    (net (code "83") (name "Net-(U12-OUT2)") (class "Default")
      (node (ref "D11") (pin "2") (pinfunction "2_2") (pintype "passive"))
      (node (ref "U12") (pin "7") (pinfunction "OUT2_7") (pintype "input"))
    )
    (net (code "84") (name "Net-(U12-OUT3)") (class "Default")
      (node (ref "D13") (pin "2") (pinfunction "2_2") (pintype "passive"))
      (node (ref "U12") (pin "8") (pinfunction "OUT3_8") (pintype "input"))
    )
    (net (code "85") (name "Net-(U12-OUT4)") (class "Default")
      (node (ref "D15") (pin "2") (pinfunction "2_2") (pintype "passive"))
      (node (ref "U12") (pin "9") (pinfunction "OUT4_9") (pintype "input"))
    )
    (net (code "86") (name "Net-(U12-OUT5)") (class "Default")
      (node (ref "D18") (pin "2") (pinfunction "2_2") (pintype "passive"))
      (node (ref "U12") (pin "10") (pinfunction "OUT5_10") (pintype "input"))
    )
    (net (code "87") (name "Net-(U12-OUT6)") (class "Default")
      (node (ref "D20") (pin "2") (pinfunction "2_2") (pintype "passive"))
      (node (ref "U12") (pin "11") (pinfunction "OUT6_11") (pintype "input"))
    )
    (net (code "88") (name "Net-(U12-OUT7)") (class "Default")
      (node (ref "D22") (pin "2") (pinfunction "2_2") (pintype "passive"))
      (node (ref "U12") (pin "12") (pinfunction "OUT7_12") (pintype "input"))
    )
    (net (code "89") (name "Net-(U12-OUT8)") (class "Default")
      (node (ref "D25") (pin "2") (pinfunction "2_2") (pintype "passive"))
      (node (ref "U12") (pin "13") (pinfunction "OUT8_13") (pintype "input"))
    )
    (net (code "90") (name "Net-(U12-OUT9)") (class "Default")
      (node (ref "D27") (pin "2") (pinfunction "2_2") (pintype "passive"))
      (node (ref "U12") (pin "14") (pinfunction "OUT9_14") (pintype "input"))
    )
    (net (code "91") (name "Net-(U12-OUT10)") (class "Default")
      (node (ref "D30") (pin "2") (pinfunction "2_2") (pintype "passive"))
      (node (ref "U12") (pin "15") (pinfunction "OUT10_15") (pintype "input"))
    )
    (net (code "92") (name "Net-(U12-OUT11)") (class "Default")
      (node (ref "D32") (pin "2") (pinfunction "2_2") (pintype "passive"))
      (node (ref "U12") (pin "16") (pinfunction "OUT11_16") (pintype "input"))
    )
    (net (code "93") (name "Net-(U12-OUT12)") (class "Default")
      (node (ref "D34") (pin "2") (pinfunction "2_2") (pintype "passive"))
      (node (ref "U12") (pin "17") (pinfunction "OUT12_17") (pintype "input"))
    )
    (net (code "94") (name "Net-(U12-OUT13)") (class "Default")
      (node (ref "D36") (pin "2") (pinfunction "2_2") (pintype "passive"))
      (node (ref "U12") (pin "18") (pinfunction "OUT13_18") (pintype "input"))
    )
    (net (code "95") (name "Net-(U12-OUT14)") (class "Default")
      (node (ref "D38") (pin "2") (pinfunction "2_2") (pintype "passive"))
      (node (ref "U12") (pin "19") (pinfunction "OUT14_19") (pintype "input"))
    )
    (net (code "96") (name "Net-(U12-OUT15)") (class "Default")
      (node (ref "D40") (pin "2") (pinfunction "2_2") (pintype "passive"))
      (node (ref "U12") (pin "20") (pinfunction "OUT15_20") (pintype "input"))
    )
    (net (code "97") (name "Net-(U12-OUT16)") (class "Default")
      (node (ref "D42") (pin "2") (pinfunction "2_2") (pintype "passive"))
      (node (ref "U12") (pin "21") (pinfunction "OUT16_21") (pintype "input"))
    )
    (net (code "98") (name "Net-(U12-OUT17)") (class "Default")
      (node (ref "D44") (pin "2") (pinfunction "2_2") (pintype "passive"))
      (node (ref "U12") (pin "22") (pinfunction "OUT17_22") (pintype "input"))
    )
    (net (code "99") (name "Net-(U12-OUT18)") (class "Default")
      (node (ref "D46") (pin "2") (pinfunction "2_2") (pintype "passive"))
      (node (ref "U12") (pin "23") (pinfunction "OUT18_23") (pintype "input"))
    )
    (net (code "100") (name "Net-(U12-OUT19)") (class "Default")
      (node (ref "D48") (pin "2") (pinfunction "2_2") (pintype "passive"))
      (node (ref "U12") (pin "24") (pinfunction "OUT19_24") (pintype "input"))
    )
    (net (code "101") (name "Net-(U12-OUT20)") (class "Default")
      (node (ref "D50") (pin "2") (pinfunction "2_2") (pintype "passive"))
      (node (ref "U12") (pin "25") (pinfunction "OUT20_25") (pintype "input"))
    )
    (net (code "102") (name "Net-(U12-OUT21)") (class "Default")
      (node (ref "D52") (pin "2") (pinfunction "2_2") (pintype "passive"))
      (node (ref "U12") (pin "26") (pinfunction "OUT21_26") (pintype "input"))
    )
    (net (code "103") (name "Net-(U12-OUT22)") (class "Default")
      (node (ref "D54") (pin "2") (pinfunction "2_2") (pintype "passive"))
      (node (ref "U12") (pin "27") (pinfunction "OUT22_27") (pintype "input"))
    )
    (net (code "104") (name "Net-(U12-OUT23)") (class "Default")
      (node (ref "D56") (pin "2") (pinfunction "2_2") (pintype "passive"))
      (node (ref "U12") (pin "28") (pinfunction "OUT23_28") (pintype "input"))
    )
    (net (code "105") (name "Net-(U13-PROG)") (class "Default")
      (node (ref "R30") (pin "1") (pinfunction "1_1") (pintype "passive"))
      (node (ref "U13") (pin "6") (pinfunction "PROG_6") (pintype "output"))
    )
    (net (code "106") (name "Net-(U13-STAT1)") (class "Default")
      (node (ref "R26") (pin "1") (pinfunction "1_1") (pintype "passive"))
      (node (ref "U13") (pin "3") (pinfunction "STAT1_3") (pintype "input"))
    )
    (net (code "107") (name "Net-(U13-STAT2)") (class "Default")
      (node (ref "R27") (pin "1") (pinfunction "1_1") (pintype "passive"))
      (node (ref "U13") (pin "4") (pinfunction "STAT2_4") (pintype "input"))
    )
    (net (code "108") (name "Net-(U13-THERM)") (class "Default")
      (node (ref "R28") (pin "1") (pinfunction "1_1") (pintype "passive"))
      (node (ref "U13") (pin "8") (pinfunction "THERM_8") (pintype "input"))
    )
    (net (code "109") (name "Net-(U13-~{PG})") (class "Default")
      (node (ref "R29") (pin "1") (pinfunction "1_1") (pintype "passive"))
      (node (ref "U13") (pin "7") (pinfunction "~{PG}_7") (pintype "input"))
    )
    (net (code "110") (name "Net-(U14-VDD)") (class "Default")
      (node (ref "C35") (pin "2") (pinfunction "2_2") (pintype "passive"))
      (node (ref "R31") (pin "1") (pinfunction "1_1") (pintype "passive"))
      (node (ref "U14") (pin "5") (pinfunction "VDD_5") (pintype "input"))
    )
    (net (code "111") (name "Net-(U14-VM)") (class "Default")
      (node (ref "R35") (pin "1") (pinfunction "1_1") (pintype "passive"))
      (node (ref "U14") (pin "2") (pinfunction "VM_2") (pintype "input"))
    )
    (net (code "112") (name "Net-(Y1-E{slash}D)") (class "Default")
      (node (ref "R25") (pin "1") (pinfunction "1_1") (pintype "passive"))
      (node (ref "Y1") (pin "1") (pinfunction "E/D_1") (pintype "passive"))
    )
    (net (code "113") (name "RESET") (class "Default")
      (node (ref "C14") (pin "2") (pinfunction "2_2") (pintype "passive"))
      (node (ref "R20") (pin "1") (pinfunction "1_1") (pintype "passive"))
      (node (ref "U10") (pin "40") (pinfunction "/RESET_40") (pintype "input"))
    )
    (net (code "114") (name "SER_D0") (class "Default")
      (node (ref "U10") (pin "12") (pinfunction "PA07/I7/AIN7/SERCOM0.3/I2SD0_12") (pintype "bidirectional"))
      (node (ref "U11") (pin "4") (pinfunction "SIN_4") (pintype "input"))
    )
    (net (code "115") (name "SER_D1") (class "Default")
      (node (ref "U11") (pin "29") (pinfunction "SOUT_29") (pintype "input"))
      (node (ref "U12") (pin "4") (pinfunction "SIN_4") (pintype "input"))
    )
    (net (code "116") (name "VBAT") (class "Default")
      (node (ref "C30") (pin "2") (pinfunction "2_2") (pintype "passive"))
      (node (ref "J3") (pin "1") (pinfunction "1_1") (pintype "passive"))
      (node (ref "Q1") (pin "2") (pinfunction "D_2") (pintype "passive"))
      (node (ref "R31") (pin "2") (pinfunction "2_2") (pintype "passive"))
      (node (ref "U13") (pin "10") (pinfunction "VBAT_10") (pintype "power_in"))
      (node (ref "U13") (pin "9") (pinfunction "VBAT_9") (pintype "power_in"))
      (node (ref "U15") (pin "2") (pinfunction "VDD_2") (pintype "power_in"))
    )
    (net (code "117") (name "VBUS") (class "Default")
      (node (ref "C32") (pin "2") (pinfunction "2_2") (pintype "passive"))
      (node (ref "D16") (pin "1") (pinfunction "1_1") (pintype "passive"))
      (node (ref "D23") (pin "1") (pinfunction "1_1") (pintype "passive"))
      (node (ref "D28") (pin "1") (pinfunction "1_1") (pintype "passive"))
      (node (ref "D3") (pin "1") (pinfunction "A_1") (pintype "passive"))
      (node (ref "FB1") (pin "2") (pinfunction "2_2") (pintype "passive"))
      (node (ref "Q1") (pin "1") (pinfunction "G_1") (pintype "passive"))
      (node (ref "R23") (pin "2") (pinfunction "2_2") (pintype "passive"))
      (node (ref "U1") (pin "5") (pinfunction "VP_5") (pintype "passive"))
      (node (ref "U13") (pin "1") (pinfunction "VDD_1") (pintype "power_in"))
      (node (ref "U13") (pin "2") (pinfunction "VDD_2") (pintype "power_in"))
    )
    (net (code "118") (name "V_REF") (class "Default")
      (node (ref "D2") (pin "2") (pinfunction "K_2") (pintype "passive"))
      (node (ref "R16") (pin "2") (pinfunction "2_2") (pintype "passive"))
      (node (ref "R7") (pin "2") (pinfunction "2_2") (pintype "passive"))
      (node (ref "U4") (pin "3") (pinfunction "+_3") (pintype "passive"))
      (node (ref "U6") (pin "3") (pinfunction "+_3") (pintype "passive"))
    )
    (net (code "119") (name "V_UNREG") (class "Default")
      (node (ref "C15") (pin "2") (pinfunction "2_2") (pintype "passive"))
      (node (ref "C21") (pin "2") (pinfunction "2_2") (pintype "passive"))
      (node (ref "C25") (pin "1") (pinfunction "1_1") (pintype "passive"))
      (node (ref "C26") (pin "1") (pinfunction "1_1") (pintype "passive"))
      (node (ref "C28") (pin "1") (pinfunction "1_1") (pintype "passive"))
      (node (ref "C29") (pin "1") (pinfunction "1_1") (pintype "passive"))
      (node (ref "D10") (pin "1") (pinfunction "1_1") (pintype "passive"))
      (node (ref "D11") (pin "1") (pinfunction "1_1") (pintype "passive"))
      (node (ref "D12") (pin "1") (pinfunction "1_1") (pintype "passive"))
      (node (ref "D13") (pin "1") (pinfunction "1_1") (pintype "passive"))
      (node (ref "D14") (pin "1") (pinfunction "1_1") (pintype "passive"))
      (node (ref "D15") (pin "1") (pinfunction "1_1") (pintype "passive"))
      (node (ref "D17") (pin "1") (pinfunction "1_1") (pintype "passive"))
      (node (ref "D18") (pin "1") (pinfunction "1_1") (pintype "passive"))
      (node (ref "D19") (pin "1") (pinfunction "1_1") (pintype "passive"))
      (node (ref "D20") (pin "1") (pinfunction "1_1") (pintype "passive"))
      (node (ref "D21") (pin "1") (pinfunction "1_1") (pintype "passive"))
      (node (ref "D22") (pin "1") (pinfunction "1_1") (pintype "passive"))
      (node (ref "D24") (pin "1") (pinfunction "1_1") (pintype "passive"))
      (node (ref "D25") (pin "1") (pinfunction "1_1") (pintype "passive"))
      (node (ref "D26") (pin "1") (pinfunction "1_1") (pintype "passive"))
      (node (ref "D27") (pin "1") (pinfunction "1_1") (pintype "passive"))
      (node (ref "D29") (pin "1") (pinfunction "1_1") (pintype "passive"))
      (node (ref "D30") (pin "1") (pinfunction "1_1") (pintype "passive"))
      (node (ref "D31") (pin "1") (pinfunction "1_1") (pintype "passive"))
      (node (ref "D32") (pin "1") (pinfunction "1_1") (pintype "passive"))
      (node (ref "D33") (pin "1") (pinfunction "1_1") (pintype "passive"))
      (node (ref "D34") (pin "1") (pinfunction "1_1") (pintype "passive"))
      (node (ref "D35") (pin "1") (pinfunction "1_1") (pintype "passive"))
      (node (ref "D36") (pin "1") (pinfunction "1_1") (pintype "passive"))
      (node (ref "D37") (pin "1") (pinfunction "1_1") (pintype "passive"))
      (node (ref "D38") (pin "1") (pinfunction "1_1") (pintype "passive"))
      (node (ref "D39") (pin "1") (pinfunction "1_1") (pintype "passive"))
      (node (ref "D40") (pin "1") (pinfunction "1_1") (pintype "passive"))
      (node (ref "D41") (pin "1") (pinfunction "1_1") (pintype "passive"))
      (node (ref "D42") (pin "1") (pinfunction "1_1") (pintype "passive"))
      (node (ref "D43") (pin "1") (pinfunction "1_1") (pintype "passive"))
      (node (ref "D44") (pin "1") (pinfunction "1_1") (pintype "passive"))
      (node (ref "D45") (pin "1") (pinfunction "1_1") (pintype "passive"))
      (node (ref "D46") (pin "1") (pinfunction "1_1") (pintype "passive"))
      (node (ref "D47") (pin "1") (pinfunction "1_1") (pintype "passive"))
      (node (ref "D48") (pin "1") (pinfunction "1_1") (pintype "passive"))
      (node (ref "D49") (pin "1") (pinfunction "1_1") (pintype "passive"))
      (node (ref "D50") (pin "1") (pinfunction "1_1") (pintype "passive"))
      (node (ref "D51") (pin "1") (pinfunction "1_1") (pintype "passive"))
      (node (ref "D52") (pin "1") (pinfunction "1_1") (pintype "passive"))
      (node (ref "D53") (pin "1") (pinfunction "1_1") (pintype "passive"))
      (node (ref "D54") (pin "1") (pinfunction "1_1") (pintype "passive"))
      (node (ref "D55") (pin "1") (pinfunction "1_1") (pintype "passive"))
      (node (ref "D56") (pin "1") (pinfunction "1_1") (pintype "passive"))
      (node (ref "D6") (pin "1") (pinfunction "1_1") (pintype "passive"))
      (node (ref "D7") (pin "1") (pinfunction "1_1") (pintype "passive"))
      (node (ref "D8") (pin "1") (pinfunction "1_1") (pintype "passive"))
      (node (ref "D9") (pin "1") (pinfunction "1_1") (pintype "passive"))
      (node (ref "Q2") (pin "2") (pinfunction "D_2") (pintype "passive"))
      (node (ref "U8") (pin "1") (pinfunction "VIN_1") (pintype "passive"))
      (node (ref "U8") (pin "3") (pinfunction "EN_3") (pintype "passive"))
      (node (ref "U9") (pin "1") (pinfunction "VIN_1") (pintype "passive"))
      (node (ref "U9") (pin "3") (pinfunction "EN_3") (pintype "passive"))
    )
    (net (code "120") (name "unconnected-(J2-R-Pad2)") (class "Default")
      (node (ref "J2") (pin "2") (pinfunction "R_2") (pintype "input+no_connect"))
    )
    (net (code "121") (name "unconnected-(S2-Pad3)") (class "Default")
      (node (ref "S2") (pin "3") (pinfunction "3_3") (pintype "passive+no_connect"))
    )
    (net (code "122") (name "unconnected-(U10-PA01{slash}EINT1{slash}SERCOM1.1-Pad2)") (class "Default")
      (node (ref "U10") (pin "2") (pinfunction "PA01/EINT1/SERCOM1.1_2") (pintype "bidirectional+no_connect"))
    )
    (net (code "123") (name "unconnected-(U10-PA03{slash}EINT3{slash}VREFA{slash}AIN1-Pad4)") (class "Default")
      (node (ref "U10") (pin "4") (pinfunction "PA03/EINT3/VREFA/AIN1_4") (pintype "bidirectional+no_connect"))
    )
    (net (code "124") (name "unconnected-(U10-PA06{slash}EINT6{slash}AIN6{slash}SERCOM0.2-Pad11)") (class "Default")
      (node (ref "U10") (pin "11") (pinfunction "PA06/EINT6/AIN6/SERCOM0.2_11") (pintype "bidirectional+no_connect"))
    )
    (net (code "125") (name "unconnected-(U10-PA12{slash}I12{slash}I2C{slash}SERCOM+4.0-Pad21)") (class "Default")
      (node (ref "U10") (pin "21") (pinfunction "PA12/I12/I2C/SERCOM+4.0_21") (pintype "bidirectional+no_connect"))
    )
    (net (code "126") (name "unconnected-(U10-PA13{slash}I13{slash}I2C{slash}SERCOM+4.1-Pad22)") (class "Default")
      (node (ref "U10") (pin "22") (pinfunction "PA13/I13/I2C/SERCOM+4.1_22") (pintype "bidirectional+no_connect"))
    )
    (net (code "127") (name "unconnected-(U10-PA14{slash}I14{slash}SERCOM2+4.2-Pad23)") (class "Default")
      (node (ref "U10") (pin "23") (pinfunction "PA14/I14/SERCOM2+4.2_23") (pintype "bidirectional+no_connect"))
    )
    (net (code "128") (name "unconnected-(U10-PA15{slash}I15{slash}SERCOM3+4.3-Pad24)") (class "Default")
      (node (ref "U10") (pin "24") (pinfunction "PA15/I15/SERCOM3+4.3_24") (pintype "bidirectional+no_connect"))
    )
    (net (code "129") (name "unconnected-(U10-PA16{slash}I2C{slash}I0{slash}SERCOM1+3.0-Pad25)") (class "Default")
      (node (ref "U10") (pin "25") (pinfunction "PA16/I2C/I0/SERCOM1+3.0_25") (pintype "bidirectional+no_connect"))
    )
    (net (code "130") (name "unconnected-(U10-PA17{slash}I2C{slash}I1{slash}SERCOM1+3.1-Pad26)") (class "Default")
      (node (ref "U10") (pin "26") (pinfunction "PA17/I2C/I1/SERCOM1+3.1_26") (pintype "bidirectional+no_connect"))
    )
    (net (code "131") (name "unconnected-(U10-PA18{slash}I2{slash}SERCOM1+3.2-Pad27)") (class "Default")
      (node (ref "U10") (pin "27") (pinfunction "PA18/I2/SERCOM1+3.2_27") (pintype "bidirectional+no_connect"))
    )
    (net (code "132") (name "unconnected-(U10-PA19{slash}I3{slash}I0{slash}SERCOM1+3.3{slash}I2SD0-Pad28)") (class "Default")
      (node (ref "U10") (pin "28") (pinfunction "PA19/I3/I0/SERCOM1+3.3/I2SD0_28") (pintype "bidirectional+no_connect"))
    )
    (net (code "133") (name "unconnected-(U10-PA20{slash}I4{slash}SERCOM1+5.2{slash}I2SSC-Pad29)") (class "Default")
      (node (ref "U10") (pin "29") (pinfunction "PA20/I4/SERCOM1+5.2/I2SSC_29") (pintype "bidirectional+no_connect"))
    )
    (net (code "134") (name "unconnected-(U10-PA21{slash}I5{slash}SERCOM1+5.3{slash}I2SFS0-Pad30)") (class "Default")
      (node (ref "U10") (pin "30") (pinfunction "PA21/I5/SERCOM1+5.3/I2SFS0_30") (pintype "bidirectional+no_connect"))
    )
    (net (code "135") (name "unconnected-(U10-PA22{slash}I2C{slash}I6{slash}SERCOM3+5.0-Pad31)") (class "Default")
      (node (ref "U10") (pin "31") (pinfunction "PA22/I2C/I6/SERCOM3+5.0_31") (pintype "bidirectional+no_connect"))
    )
    (net (code "136") (name "unconnected-(U10-PA23{slash}I2C{slash}I7{slash}SERCOM3+5.1{slash}SOF-Pad32)") (class "Default")
      (node (ref "U10") (pin "32") (pinfunction "PA23/I2C/I7/SERCOM3+5.1/SOF_32") (pintype "bidirectional+no_connect"))
    )
    (net (code "137") (name "unconnected-(U10-PA27{slash}I15-Pad39)") (class "Default")
      (node (ref "U10") (pin "39") (pinfunction "PA27/I15_39") (pintype "bidirectional+no_connect"))
    )
    (net (code "138") (name "unconnected-(U10-PA28{slash}I8-Pad41)") (class "Default")
      (node (ref "U10") (pin "41") (pinfunction "PA28/I8_41") (pintype "bidirectional+no_connect"))
    )
    (net (code "139") (name "unconnected-(U10-PA30{slash}I10{slash}SECOM1.2{slash}SWCLK-Pad45)") (class "Default")
      (node (ref "U10") (pin "45") (pinfunction "PA30/I10/SECOM1.2/SWCLK_45") (pintype "bidirectional+no_connect"))
    )
    (net (code "140") (name "unconnected-(U10-PA31{slash}I11{slash}SECOM1.3{slash}SWDIO-Pad46)") (class "Default")
      (node (ref "U10") (pin "46") (pinfunction "PA31/I11/SECOM1.3/SWDIO_46") (pintype "bidirectional+no_connect"))
    )
    (net (code "141") (name "unconnected-(U10-PB02{slash}I2{slash}AIN10{slash}SERCOM5.0-Pad47)") (class "Default")
      (node (ref "U10") (pin "47") (pinfunction "PB02/I2/AIN10/SERCOM5.0_47") (pintype "bidirectional+no_connect"))
    )
    (net (code "142") (name "unconnected-(U10-PB10{slash}I10{slash}SERCOM4.2{slash}I2SMC-Pad19)") (class "Default")
      (node (ref "U10") (pin "19") (pinfunction "PB10/I10/SERCOM4.2/I2SMC_19") (pintype "bidirectional+no_connect"))
    )
    (net (code "143") (name "unconnected-(U10-PB11{slash}I11{slash}SERCOM4.3{slash}I2SCL-Pad20)") (class "Default")
      (node (ref "U10") (pin "20") (pinfunction "PB11/I11/SERCOM4.3/I2SCL_20") (pintype "bidirectional+no_connect"))
    )
    (net (code "144") (name "unconnected-(U10-PB22{slash}I6{slash}SERCOM5.2-Pad37)") (class "Default")
      (node (ref "U10") (pin "37") (pinfunction "PB22/I6/SERCOM5.2_37") (pintype "bidirectional+no_connect"))
    )
    (net (code "145") (name "unconnected-(U10-PB23{slash}I7{slash}SERCOM5.3-Pad38)") (class "Default")
      (node (ref "U10") (pin "38") (pinfunction "PB23/I7/SERCOM5.3_38") (pintype "bidirectional+no_connect"))
    )
    (net (code "146") (name "unconnected-(U12-SOUT-Pad29)") (class "Default")
      (node (ref "U12") (pin "29") (pinfunction "SOUT_29") (pintype "input+no_connect"))
    )
  )
)
